# DAC_JESD204B.net
KiCad netlist of a schematic drawn in Altium Designer
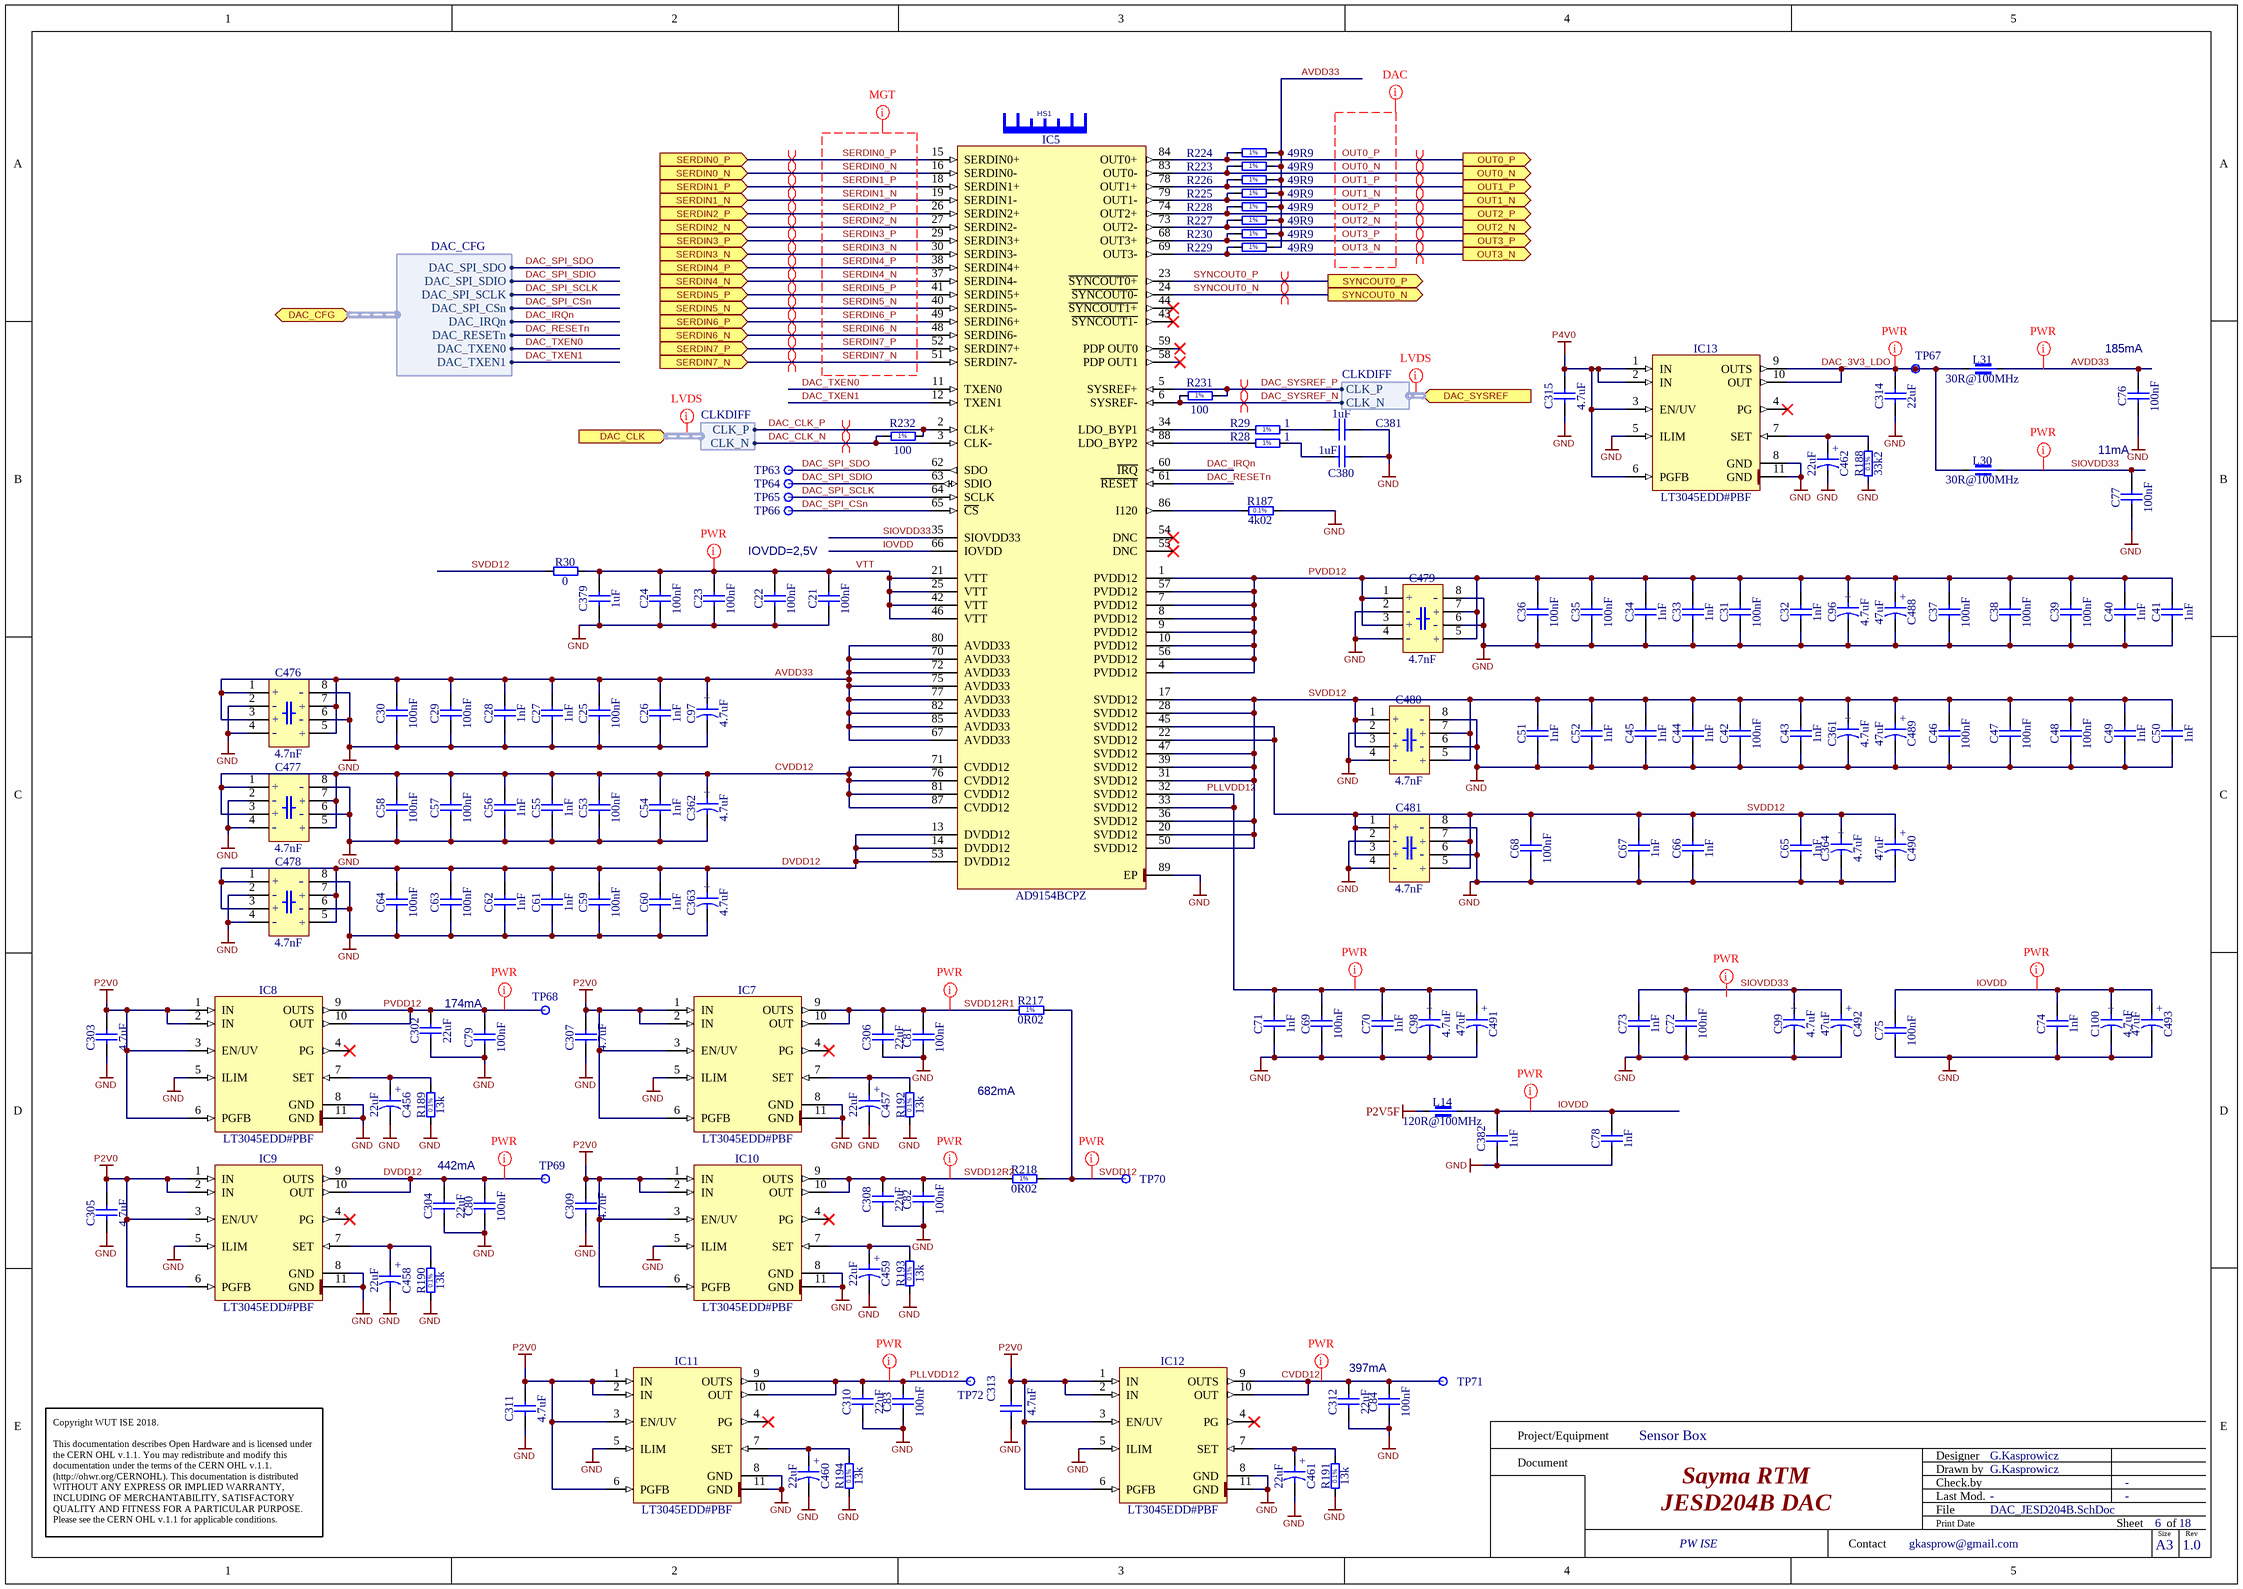
[diagram p0: DAC_JESD204B.SchDoc]

(export (version "E")
  (design (tool "Eeschema 10.0.6"))
  (components
    (comp (ref "C21")
      (value "100nF")
      (footprint "CAPC0603X33N")
      (description "Non-polarised capacitor")
      (fields
        (field (name "MANUFACTURER PART NUMBER") "CC0201_100NF_6.3V_10%_X5R")
        (field (name "MANUFACTURER") "GENERIC")
        (field (name "AUTHOR") "CERN DEM JLC")
      )
      (libsource (lib "Capacitors") (part "Capacitor - non polarized"))
    )
    (comp (ref "C22")
      (value "100nF")
      (footprint "CAPC0603X33N")
      (description "Non-polarised capacitor")
      (fields
        (field (name "MANUFACTURER PART NUMBER") "CC0201_100NF_6.3V_10%_X5R")
        (field (name "MANUFACTURER") "GENERIC")
        (field (name "AUTHOR") "CERN DEM JLC")
      )
      (libsource (lib "Capacitors") (part "Capacitor - non polarized"))
    )
    (comp (ref "C23")
      (value "100nF")
      (footprint "CAPC0603X33N")
      (description "Non-polarised capacitor")
      (fields
        (field (name "MANUFACTURER PART NUMBER") "CC0201_100NF_6.3V_10%_X5R")
        (field (name "MANUFACTURER") "GENERIC")
        (field (name "AUTHOR") "CERN DEM JLC")
      )
      (libsource (lib "Capacitors") (part "Capacitor - non polarized"))
    )
    (comp (ref "C24")
      (value "100nF")
      (footprint "CAPC0603X33N")
      (description "Non-polarised capacitor")
      (fields
        (field (name "MANUFACTURER PART NUMBER") "CC0201_100NF_6.3V_10%_X5R")
        (field (name "MANUFACTURER") "GENERIC")
        (field (name "AUTHOR") "CERN DEM JLC")
      )
      (libsource (lib "Capacitors") (part "Capacitor - non polarized"))
    )
    (comp (ref "C25")
      (value "100nF")
      (footprint "CAPC0603X33N")
      (description "Non-polarised capacitor")
      (fields
        (field (name "MANUFACTURER PART NUMBER") "CC0201_100NF_6.3V_10%_X5R")
        (field (name "MANUFACTURER") "GENERIC")
        (field (name "AUTHOR") "CERN DEM JLC")
      )
      (libsource (lib "Capacitors") (part "Capacitor - non polarized"))
    )
    (comp (ref "C26")
      (value "1nF")
      (footprint "CAPC0603X33N")
      (description "Non-polarised capacitor")
      (fields
        (field (name "MANUFACTURER PART NUMBER") "CC0201_1NF_16V_10%_X5R")
        (field (name "MANUFACTURER") "GENERIC")
        (field (name "AUTHOR") "CERN DEM JLC")
      )
      (libsource (lib "Capacitors") (part "Capacitor - non polarized"))
    )
    (comp (ref "C27")
      (value "1nF")
      (footprint "CAPC0603X33N")
      (description "Non-polarised capacitor")
      (fields
        (field (name "MANUFACTURER PART NUMBER") "CC0201_1NF_16V_10%_X5R")
        (field (name "MANUFACTURER") "GENERIC")
        (field (name "AUTHOR") "CERN DEM JLC")
      )
      (libsource (lib "Capacitors") (part "Capacitor - non polarized"))
    )
    (comp (ref "C28")
      (value "1nF")
      (footprint "CAPC0603X33N")
      (description "Non-polarised capacitor")
      (fields
        (field (name "MANUFACTURER PART NUMBER") "CC0201_1NF_16V_10%_X5R")
        (field (name "MANUFACTURER") "GENERIC")
        (field (name "AUTHOR") "CERN DEM JLC")
      )
      (libsource (lib "Capacitors") (part "Capacitor - non polarized"))
    )
    (comp (ref "C29")
      (value "100nF")
      (footprint "CAPC0603X33N")
      (description "Non-polarised capacitor")
      (fields
        (field (name "MANUFACTURER PART NUMBER") "CC0201_100NF_6.3V_10%_X5R")
        (field (name "MANUFACTURER") "GENERIC")
        (field (name "AUTHOR") "CERN DEM JLC")
      )
      (libsource (lib "Capacitors") (part "Capacitor - non polarized"))
    )
    (comp (ref "C30")
      (value "100nF")
      (footprint "CAPC0603X33N")
      (description "Non-polarised capacitor")
      (fields
        (field (name "MANUFACTURER PART NUMBER") "CC0201_100NF_6.3V_10%_X5R")
        (field (name "MANUFACTURER") "GENERIC")
        (field (name "AUTHOR") "CERN DEM JLC")
      )
      (libsource (lib "Capacitors") (part "Capacitor - non polarized"))
    )
    (comp (ref "C31")
      (value "100nF")
      (footprint "CAPC0603X33N")
      (description "Non-polarised capacitor")
      (fields
        (field (name "MANUFACTURER PART NUMBER") "CC0201_100NF_6.3V_10%_X5R")
        (field (name "MANUFACTURER") "GENERIC")
        (field (name "AUTHOR") "CERN DEM JLC")
      )
      (libsource (lib "Capacitors") (part "Capacitor - non polarized"))
    )
    (comp (ref "C32")
      (value "1nF")
      (footprint "CAPC0603X33N")
      (description "Non-polarised capacitor")
      (fields
        (field (name "MANUFACTURER PART NUMBER") "CC0201_1NF_16V_10%_X5R")
        (field (name "MANUFACTURER") "GENERIC")
        (field (name "AUTHOR") "CERN DEM JLC")
      )
      (libsource (lib "Capacitors") (part "Capacitor - non polarized"))
    )
    (comp (ref "C33")
      (value "1nF")
      (footprint "CAPC0603X33N")
      (description "Non-polarised capacitor")
      (fields
        (field (name "MANUFACTURER PART NUMBER") "CC0201_1NF_16V_10%_X5R")
        (field (name "MANUFACTURER") "GENERIC")
        (field (name "AUTHOR") "CERN DEM JLC")
      )
      (libsource (lib "Capacitors") (part "Capacitor - non polarized"))
    )
    (comp (ref "C34")
      (value "1nF")
      (footprint "CAPC0603X33N")
      (description "Non-polarised capacitor")
      (fields
        (field (name "MANUFACTURER PART NUMBER") "CC0201_1NF_16V_10%_X5R")
        (field (name "MANUFACTURER") "GENERIC")
        (field (name "AUTHOR") "CERN DEM JLC")
      )
      (libsource (lib "Capacitors") (part "Capacitor - non polarized"))
    )
    (comp (ref "C35")
      (value "100nF")
      (footprint "CAPC0603X33N")
      (description "Non-polarised capacitor")
      (fields
        (field (name "MANUFACTURER PART NUMBER") "CC0201_100NF_6.3V_10%_X5R")
        (field (name "MANUFACTURER") "GENERIC")
        (field (name "AUTHOR") "CERN DEM JLC")
      )
      (libsource (lib "Capacitors") (part "Capacitor - non polarized"))
    )
    (comp (ref "C36")
      (value "100nF")
      (footprint "CAPC0603X33N")
      (description "Non-polarised capacitor")
      (fields
        (field (name "MANUFACTURER PART NUMBER") "CC0201_100NF_6.3V_10%_X5R")
        (field (name "MANUFACTURER") "GENERIC")
        (field (name "AUTHOR") "CERN DEM JLC")
      )
      (libsource (lib "Capacitors") (part "Capacitor - non polarized"))
    )
    (comp (ref "C37")
      (value "100nF")
      (footprint "CAPC0603X33N")
      (description "Non-polarised capacitor")
      (fields
        (field (name "MANUFACTURER PART NUMBER") "CC0201_100NF_6.3V_10%_X5R")
        (field (name "MANUFACTURER") "GENERIC")
        (field (name "AUTHOR") "CERN DEM JLC")
      )
      (libsource (lib "Capacitors") (part "Capacitor - non polarized"))
    )
    (comp (ref "C38")
      (value "100nF")
      (footprint "CAPC0603X33N")
      (description "Non-polarised capacitor")
      (fields
        (field (name "MANUFACTURER PART NUMBER") "CC0201_100NF_6.3V_10%_X5R")
        (field (name "MANUFACTURER") "GENERIC")
        (field (name "AUTHOR") "CERN DEM JLC")
      )
      (libsource (lib "Capacitors") (part "Capacitor - non polarized"))
    )
    (comp (ref "C39")
      (value "100nF")
      (footprint "CAPC0603X33N")
      (description "Non-polarised capacitor")
      (fields
        (field (name "MANUFACTURER PART NUMBER") "CC0201_100NF_6.3V_10%_X5R")
        (field (name "MANUFACTURER") "GENERIC")
        (field (name "AUTHOR") "CERN DEM JLC")
      )
      (libsource (lib "Capacitors") (part "Capacitor - non polarized"))
    )
    (comp (ref "C40")
      (value "1nF")
      (footprint "CAPC0603X33N")
      (description "Non-polarised capacitor")
      (fields
        (field (name "MANUFACTURER PART NUMBER") "CC0201_1NF_16V_10%_X5R")
        (field (name "MANUFACTURER") "GENERIC")
        (field (name "AUTHOR") "CERN DEM JLC")
      )
      (libsource (lib "Capacitors") (part "Capacitor - non polarized"))
    )
    (comp (ref "C41")
      (value "1nF")
      (footprint "CAPC0603X33N")
      (description "Non-polarised capacitor")
      (fields
        (field (name "MANUFACTURER PART NUMBER") "CC0201_1NF_16V_10%_X5R")
        (field (name "MANUFACTURER") "GENERIC")
        (field (name "AUTHOR") "CERN DEM JLC")
      )
      (libsource (lib "Capacitors") (part "Capacitor - non polarized"))
    )
    (comp (ref "C42")
      (value "100nF")
      (footprint "CAPC0603X33N")
      (description "Non-polarised capacitor")
      (fields
        (field (name "MANUFACTURER PART NUMBER") "CC0201_100NF_6.3V_10%_X5R")
        (field (name "MANUFACTURER") "GENERIC")
        (field (name "AUTHOR") "CERN DEM JLC")
      )
      (libsource (lib "Capacitors") (part "Capacitor - non polarized"))
    )
    (comp (ref "C43")
      (value "1nF")
      (footprint "CAPC0603X33N")
      (description "Non-polarised capacitor")
      (fields
        (field (name "MANUFACTURER PART NUMBER") "CC0201_1NF_16V_10%_X5R")
        (field (name "MANUFACTURER") "GENERIC")
        (field (name "AUTHOR") "CERN DEM JLC")
      )
      (libsource (lib "Capacitors") (part "Capacitor - non polarized"))
    )
    (comp (ref "C44")
      (value "1nF")
      (footprint "CAPC0603X33N")
      (description "Non-polarised capacitor")
      (fields
        (field (name "MANUFACTURER PART NUMBER") "CC0201_1NF_16V_10%_X5R")
        (field (name "MANUFACTURER") "GENERIC")
        (field (name "AUTHOR") "CERN DEM JLC")
      )
      (libsource (lib "Capacitors") (part "Capacitor - non polarized"))
    )
    (comp (ref "C45")
      (value "1nF")
      (footprint "CAPC0603X33N")
      (description "Non-polarised capacitor")
      (fields
        (field (name "MANUFACTURER PART NUMBER") "CC0201_1NF_16V_10%_X5R")
        (field (name "MANUFACTURER") "GENERIC")
        (field (name "AUTHOR") "CERN DEM JLC")
      )
      (libsource (lib "Capacitors") (part "Capacitor - non polarized"))
    )
    (comp (ref "C46")
      (value "100nF")
      (footprint "CAPC0603X33N")
      (description "Non-polarised capacitor")
      (fields
        (field (name "MANUFACTURER PART NUMBER") "CC0201_100NF_6.3V_10%_X5R")
        (field (name "MANUFACTURER") "GENERIC")
        (field (name "AUTHOR") "CERN DEM JLC")
      )
      (libsource (lib "Capacitors") (part "Capacitor - non polarized"))
    )
    (comp (ref "C47")
      (value "100nF")
      (footprint "CAPC0603X33N")
      (description "Non-polarised capacitor")
      (fields
        (field (name "MANUFACTURER PART NUMBER") "CC0201_100NF_6.3V_10%_X5R")
        (field (name "MANUFACTURER") "GENERIC")
        (field (name "AUTHOR") "CERN DEM JLC")
      )
      (libsource (lib "Capacitors") (part "Capacitor - non polarized"))
    )
    (comp (ref "C48")
      (value "100nF")
      (footprint "CAPC0603X33N")
      (description "Non-polarised capacitor")
      (fields
        (field (name "MANUFACTURER PART NUMBER") "CC0201_100NF_6.3V_10%_X5R")
        (field (name "MANUFACTURER") "GENERIC")
        (field (name "AUTHOR") "CERN DEM JLC")
      )
      (libsource (lib "Capacitors") (part "Capacitor - non polarized"))
    )
    (comp (ref "C49")
      (value "1nF")
      (footprint "CAPC0603X33N")
      (description "Non-polarised capacitor")
      (fields
        (field (name "MANUFACTURER PART NUMBER") "CC0201_1NF_16V_10%_X5R")
        (field (name "MANUFACTURER") "GENERIC")
        (field (name "AUTHOR") "CERN DEM JLC")
      )
      (libsource (lib "Capacitors") (part "Capacitor - non polarized"))
    )
    (comp (ref "C50")
      (value "1nF")
      (footprint "CAPC0603X33N")
      (description "Non-polarised capacitor")
      (fields
        (field (name "MANUFACTURER PART NUMBER") "CC0201_1NF_16V_10%_X5R")
        (field (name "MANUFACTURER") "GENERIC")
        (field (name "AUTHOR") "CERN DEM JLC")
      )
      (libsource (lib "Capacitors") (part "Capacitor - non polarized"))
    )
    (comp (ref "C51")
      (value "1nF")
      (footprint "CAPC0603X33N")
      (description "Non-polarised capacitor")
      (fields
        (field (name "MANUFACTURER PART NUMBER") "CC0201_1NF_16V_10%_X5R")
        (field (name "MANUFACTURER") "GENERIC")
        (field (name "AUTHOR") "CERN DEM JLC")
      )
      (libsource (lib "Capacitors") (part "Capacitor - non polarized"))
    )
    (comp (ref "C52")
      (value "1nF")
      (footprint "CAPC0603X33N")
      (description "Non-polarised capacitor")
      (fields
        (field (name "MANUFACTURER PART NUMBER") "CC0201_1NF_16V_10%_X5R")
        (field (name "MANUFACTURER") "GENERIC")
        (field (name "AUTHOR") "CERN DEM JLC")
      )
      (libsource (lib "Capacitors") (part "Capacitor - non polarized"))
    )
    (comp (ref "C53")
      (value "100nF")
      (footprint "CAPC0603X33N")
      (description "Non-polarised capacitor")
      (fields
        (field (name "MANUFACTURER PART NUMBER") "CC0201_100NF_6.3V_10%_X5R")
        (field (name "MANUFACTURER") "GENERIC")
        (field (name "AUTHOR") "CERN DEM JLC")
      )
      (libsource (lib "Capacitors") (part "Capacitor - non polarized"))
    )
    (comp (ref "C54")
      (value "1nF")
      (footprint "CAPC0603X33N")
      (description "Non-polarised capacitor")
      (fields
        (field (name "MANUFACTURER PART NUMBER") "CC0201_1NF_16V_10%_X5R")
        (field (name "MANUFACTURER") "GENERIC")
        (field (name "AUTHOR") "CERN DEM JLC")
      )
      (libsource (lib "Capacitors") (part "Capacitor - non polarized"))
    )
    (comp (ref "C55")
      (value "1nF")
      (footprint "CAPC0603X33N")
      (description "Non-polarised capacitor")
      (fields
        (field (name "MANUFACTURER PART NUMBER") "CC0201_1NF_16V_10%_X5R")
        (field (name "MANUFACTURER") "GENERIC")
        (field (name "AUTHOR") "CERN DEM JLC")
      )
      (libsource (lib "Capacitors") (part "Capacitor - non polarized"))
    )
    (comp (ref "C56")
      (value "1nF")
      (footprint "CAPC0603X33N")
      (description "Non-polarised capacitor")
      (fields
        (field (name "MANUFACTURER PART NUMBER") "CC0201_1NF_16V_10%_X5R")
        (field (name "MANUFACTURER") "GENERIC")
        (field (name "AUTHOR") "CERN DEM JLC")
      )
      (libsource (lib "Capacitors") (part "Capacitor - non polarized"))
    )
    (comp (ref "C57")
      (value "100nF")
      (footprint "CAPC0603X33N")
      (description "Non-polarised capacitor")
      (fields
        (field (name "MANUFACTURER PART NUMBER") "CC0201_100NF_6.3V_10%_X5R")
        (field (name "MANUFACTURER") "GENERIC")
        (field (name "AUTHOR") "CERN DEM JLC")
      )
      (libsource (lib "Capacitors") (part "Capacitor - non polarized"))
    )
    (comp (ref "C58")
      (value "100nF")
      (footprint "CAPC0603X33N")
      (description "Non-polarised capacitor")
      (fields
        (field (name "MANUFACTURER PART NUMBER") "CC0201_100NF_6.3V_10%_X5R")
        (field (name "MANUFACTURER") "GENERIC")
        (field (name "AUTHOR") "CERN DEM JLC")
      )
      (libsource (lib "Capacitors") (part "Capacitor - non polarized"))
    )
    (comp (ref "C59")
      (value "100nF")
      (footprint "CAPC0603X33N")
      (description "Non-polarised capacitor")
      (fields
        (field (name "MANUFACTURER PART NUMBER") "CC0201_100NF_6.3V_10%_X5R")
        (field (name "MANUFACTURER") "GENERIC")
        (field (name "AUTHOR") "CERN DEM JLC")
      )
      (libsource (lib "Capacitors") (part "Capacitor - non polarized"))
    )
    (comp (ref "C60")
      (value "1nF")
      (footprint "CAPC0603X33N")
      (description "Non-polarised capacitor")
      (fields
        (field (name "MANUFACTURER PART NUMBER") "CC0201_1NF_16V_10%_X5R")
        (field (name "MANUFACTURER") "GENERIC")
        (field (name "AUTHOR") "CERN DEM JLC")
      )
      (libsource (lib "Capacitors") (part "Capacitor - non polarized"))
    )
    (comp (ref "C61")
      (value "1nF")
      (footprint "CAPC0603X33N")
      (description "Non-polarised capacitor")
      (fields
        (field (name "MANUFACTURER PART NUMBER") "CC0201_1NF_16V_10%_X5R")
        (field (name "MANUFACTURER") "GENERIC")
        (field (name "AUTHOR") "CERN DEM JLC")
      )
      (libsource (lib "Capacitors") (part "Capacitor - non polarized"))
    )
    (comp (ref "C62")
      (value "1nF")
      (footprint "CAPC0603X33N")
      (description "Non-polarised capacitor")
      (fields
        (field (name "MANUFACTURER PART NUMBER") "CC0201_1NF_16V_10%_X5R")
        (field (name "MANUFACTURER") "GENERIC")
        (field (name "AUTHOR") "CERN DEM JLC")
      )
      (libsource (lib "Capacitors") (part "Capacitor - non polarized"))
    )
    (comp (ref "C63")
      (value "100nF")
      (footprint "CAPC0603X33N")
      (description "Non-polarised capacitor")
      (fields
        (field (name "MANUFACTURER PART NUMBER") "CC0201_100NF_6.3V_10%_X5R")
        (field (name "MANUFACTURER") "GENERIC")
        (field (name "AUTHOR") "CERN DEM JLC")
      )
      (libsource (lib "Capacitors") (part "Capacitor - non polarized"))
    )
    (comp (ref "C64")
      (value "100nF")
      (footprint "CAPC0603X33N")
      (description "Non-polarised capacitor")
      (fields
        (field (name "MANUFACTURER PART NUMBER") "CC0201_100NF_6.3V_10%_X5R")
        (field (name "MANUFACTURER") "GENERIC")
        (field (name "AUTHOR") "CERN DEM JLC")
      )
      (libsource (lib "Capacitors") (part "Capacitor - non polarized"))
    )
    (comp (ref "C65")
      (value "1nF")
      (footprint "CAPC0603X33N")
      (description "Non-polarised capacitor")
      (fields
        (field (name "MANUFACTURER PART NUMBER") "CC0201_1NF_16V_10%_X5R")
        (field (name "MANUFACTURER") "GENERIC")
        (field (name "AUTHOR") "CERN DEM JLC")
      )
      (libsource (lib "Capacitors") (part "Capacitor - non polarized"))
    )
    (comp (ref "C66")
      (value "1nF")
      (footprint "CAPC0603X33N")
      (description "Non-polarised capacitor")
      (fields
        (field (name "MANUFACTURER PART NUMBER") "CC0201_1NF_16V_10%_X5R")
        (field (name "MANUFACTURER") "GENERIC")
        (field (name "AUTHOR") "CERN DEM JLC")
      )
      (libsource (lib "Capacitors") (part "Capacitor - non polarized"))
    )
    (comp (ref "C67")
      (value "1nF")
      (footprint "CAPC0603X33N")
      (description "Non-polarised capacitor")
      (fields
        (field (name "MANUFACTURER PART NUMBER") "CC0201_1NF_16V_10%_X5R")
        (field (name "MANUFACTURER") "GENERIC")
        (field (name "AUTHOR") "CERN DEM JLC")
      )
      (libsource (lib "Capacitors") (part "Capacitor - non polarized"))
    )
    (comp (ref "C68")
      (value "100nF")
      (footprint "CAPC0603X33N")
      (description "Non-polarised capacitor")
      (fields
        (field (name "MANUFACTURER PART NUMBER") "CC0201_100NF_6.3V_10%_X5R")
        (field (name "MANUFACTURER") "GENERIC")
        (field (name "AUTHOR") "CERN DEM JLC")
      )
      (libsource (lib "Capacitors") (part "Capacitor - non polarized"))
    )
    (comp (ref "C69")
      (value "100nF")
      (footprint "CAPC0603X33N")
      (description "Non-polarised capacitor")
      (fields
        (field (name "MANUFACTURER PART NUMBER") "CC0201_100NF_6.3V_10%_X5R")
        (field (name "MANUFACTURER") "GENERIC")
        (field (name "AUTHOR") "CERN DEM JLC")
      )
      (libsource (lib "Capacitors") (part "Capacitor - non polarized"))
    )
    (comp (ref "C70")
      (value "1nF")
      (footprint "CAPC0603X33N")
      (description "Non-polarised capacitor")
      (fields
        (field (name "MANUFACTURER PART NUMBER") "CC0201_1NF_16V_10%_X5R")
        (field (name "MANUFACTURER") "GENERIC")
        (field (name "AUTHOR") "CERN DEM JLC")
      )
      (libsource (lib "Capacitors") (part "Capacitor - non polarized"))
    )
    (comp (ref "C71")
      (value "1nF")
      (footprint "CAPC0603X33N")
      (description "Non-polarised capacitor")
      (fields
        (field (name "MANUFACTURER PART NUMBER") "CC0201_1NF_16V_10%_X5R")
        (field (name "MANUFACTURER") "GENERIC")
        (field (name "AUTHOR") "CERN DEM JLC")
      )
      (libsource (lib "Capacitors") (part "Capacitor - non polarized"))
    )
    (comp (ref "C72")
      (value "100nF")
      (footprint "CAPC0603X33N")
      (description "Non-polarised capacitor")
      (fields
        (field (name "MANUFACTURER PART NUMBER") "CC0201_100NF_6.3V_10%_X5R")
        (field (name "MANUFACTURER") "GENERIC")
        (field (name "AUTHOR") "CERN DEM JLC")
      )
      (libsource (lib "Capacitors") (part "Capacitor - non polarized"))
    )
    (comp (ref "C73")
      (value "1nF")
      (footprint "CAPC0603X33N")
      (description "Non-polarised capacitor")
      (fields
        (field (name "MANUFACTURER PART NUMBER") "CC0201_1NF_16V_10%_X5R")
        (field (name "MANUFACTURER") "GENERIC")
        (field (name "AUTHOR") "CERN DEM JLC")
      )
      (libsource (lib "Capacitors") (part "Capacitor - non polarized"))
    )
    (comp (ref "C74")
      (value "1nF")
      (footprint "CAPC0603X33N")
      (description "Non-polarised capacitor")
      (fields
        (field (name "MANUFACTURER PART NUMBER") "CC0201_1NF_16V_10%_X5R")
        (field (name "MANUFACTURER") "GENERIC")
        (field (name "AUTHOR") "CERN DEM JLC")
      )
      (libsource (lib "Capacitors") (part "Capacitor - non polarized"))
    )
    (comp (ref "C75")
      (value "100nF")
      (footprint "CAPC0603X33N")
      (description "Non-polarised capacitor")
      (fields
        (field (name "MANUFACTURER PART NUMBER") "CC0201_100NF_6.3V_10%_X5R")
        (field (name "MANUFACTURER") "GENERIC")
        (field (name "AUTHOR") "CERN DEM JLC")
      )
      (libsource (lib "Capacitors") (part "Capacitor - non polarized"))
    )
    (comp (ref "C76")
      (value "100nF")
      (footprint "CAPC0603X33N")
      (description "Non-polarised capacitor")
      (fields
        (field (name "MANUFACTURER PART NUMBER") "CC0201_100NF_6.3V_10%_X5R")
        (field (name "MANUFACTURER") "GENERIC")
        (field (name "AUTHOR") "CERN DEM JLC")
      )
      (libsource (lib "Capacitors") (part "Capacitor - non polarized"))
    )
    (comp (ref "C77")
      (value "100nF")
      (footprint "CAPC0603X33N")
      (description "Non-polarised capacitor")
      (fields
        (field (name "MANUFACTURER PART NUMBER") "CC0201_100NF_6.3V_10%_X5R")
        (field (name "MANUFACTURER") "GENERIC")
        (field (name "AUTHOR") "CERN DEM JLC")
      )
      (libsource (lib "Capacitors") (part "Capacitor - non polarized"))
    )
    (comp (ref "C78")
      (value "1nF")
      (footprint "CAPC0603X33N")
      (description "Non-polarised capacitor")
      (fields
        (field (name "MANUFACTURER PART NUMBER") "CC0201_1NF_16V_10%_X5R")
        (field (name "MANUFACTURER") "GENERIC")
        (field (name "AUTHOR") "CERN DEM JLC")
      )
      (libsource (lib "Capacitors") (part "Capacitor - non polarized"))
    )
    (comp (ref "C79")
      (value "100nF")
      (footprint "CAPC0603X33N")
      (description "Non-polarised capacitor")
      (fields
        (field (name "MANUFACTURER PART NUMBER") "CC0201_100NF_6.3V_10%_X5R")
        (field (name "MANUFACTURER") "GENERIC")
        (field (name "AUTHOR") "CERN DEM JLC")
      )
      (libsource (lib "Capacitors") (part "Capacitor - non polarized"))
    )
    (comp (ref "C80")
      (value "100nF")
      (footprint "CAPC0603X33N")
      (description "Non-polarised capacitor")
      (fields
        (field (name "MANUFACTURER PART NUMBER") "CC0201_100NF_6.3V_10%_X5R")
        (field (name "MANUFACTURER") "GENERIC")
        (field (name "AUTHOR") "CERN DEM JLC")
      )
      (libsource (lib "Capacitors") (part "Capacitor - non polarized"))
    )
    (comp (ref "C81")
      (value "100nF")
      (footprint "CAPC0603X33N")
      (description "Non-polarised capacitor")
      (fields
        (field (name "MANUFACTURER PART NUMBER") "CC0201_100NF_6.3V_10%_X5R")
        (field (name "MANUFACTURER") "GENERIC")
        (field (name "AUTHOR") "CERN DEM JLC")
      )
      (libsource (lib "Capacitors") (part "Capacitor - non polarized"))
    )
    (comp (ref "C82")
      (value "100nF")
      (footprint "CAPC0603X33N")
      (description "Non-polarised capacitor")
      (fields
        (field (name "MANUFACTURER PART NUMBER") "CC0201_100NF_6.3V_10%_X5R")
        (field (name "MANUFACTURER") "GENERIC")
        (field (name "AUTHOR") "CERN DEM JLC")
      )
      (libsource (lib "Capacitors") (part "Capacitor - non polarized"))
    )
    (comp (ref "C83")
      (value "100nF")
      (footprint "CAPC0603X33N")
      (description "Non-polarised capacitor")
      (fields
        (field (name "MANUFACTURER PART NUMBER") "CC0201_100NF_6.3V_10%_X5R")
        (field (name "MANUFACTURER") "GENERIC")
        (field (name "AUTHOR") "CERN DEM JLC")
      )
      (libsource (lib "Capacitors") (part "Capacitor - non polarized"))
    )
    (comp (ref "C84")
      (value "100nF")
      (footprint "CAPC0603X33N")
      (description "Non-polarised capacitor")
      (fields
        (field (name "MANUFACTURER PART NUMBER") "CC0201_100NF_6.3V_10%_X5R")
        (field (name "MANUFACTURER") "GENERIC")
        (field (name "AUTHOR") "CERN DEM JLC")
      )
      (libsource (lib "Capacitors") (part "Capacitor - non polarized"))
    )
    (comp (ref "C96")
      (value "4.7uF")
      (footprint "CAPMP3528X210N")
      (description "Polarised capacitor")
      (fields
        (field (name "MANUFACTURER PART NUMBER") "CTE3528-21_4.7UF_35V_10%")
        (field (name "MANUFACTURER") "GENERIC")
        (field (name "AUTHOR") "CERN DEM JLC")
      )
      (libsource (lib "") (part "Capacitor - polarized_1"))
    )
    (comp (ref "C97")
      (value "4.7uF")
      (footprint "CAPMP3528X210N")
      (description "Polarised capacitor")
      (fields
        (field (name "MANUFACTURER PART NUMBER") "CTE3528-21_4.7UF_35V_10%")
        (field (name "MANUFACTURER") "GENERIC")
        (field (name "AUTHOR") "CERN DEM JLC")
      )
      (libsource (lib "") (part "Capacitor - polarized_1"))
    )
    (comp (ref "C98")
      (value "4.7uF")
      (footprint "CAPMP3528X210N")
      (description "Polarised capacitor")
      (fields
        (field (name "MANUFACTURER PART NUMBER") "CTE3528-21_4.7UF_35V_10%")
        (field (name "MANUFACTURER") "GENERIC")
        (field (name "AUTHOR") "CERN DEM JLC")
      )
      (libsource (lib "") (part "Capacitor - polarized_1"))
    )
    (comp (ref "C99")
      (value "4.7uF")
      (footprint "CAPMP3528X210N")
      (description "Polarised capacitor")
      (fields
        (field (name "MANUFACTURER PART NUMBER") "CTE3528-21_4.7UF_35V_10%")
        (field (name "MANUFACTURER") "GENERIC")
        (field (name "AUTHOR") "CERN DEM JLC")
      )
      (libsource (lib "") (part "Capacitor - polarized_1"))
    )
    (comp (ref "C100")
      (value "4.7uF")
      (footprint "CAPMP3528X210N")
      (description "Polarised capacitor")
      (fields
        (field (name "MANUFACTURER PART NUMBER") "CTE3528-21_4.7UF_35V_10%")
        (field (name "MANUFACTURER") "GENERIC")
        (field (name "AUTHOR") "CERN DEM JLC")
      )
      (libsource (lib "") (part "Capacitor - polarized_1"))
    )
    (comp (ref "C302")
      (value "22uF")
      (footprint "CAPC2012X135N")
      (description "Non-polarised capacitor")
      (fields
        (field (name "MANUFACTURER PART NUMBER") "CC0805_22UF_16V_10%_X5R")
        (field (name "MANUFACTURER") "GENERIC")
        (field (name "AUTHOR") "CERN DEM JLC")
      )
      (libsource (lib "Capacitors") (part "Capacitor - non polarized"))
    )
    (comp (ref "C303")
      (value "4.7uF")
      (footprint "CAPC1608X90N")
      (description "Non-polarised capacitor")
      (fields
        (field (name "MANUFACTURER PART NUMBER") "CC0603_4.7UF_25V_10%_X5R")
        (field (name "MANUFACTURER") "GENERIC")
        (field (name "AUTHOR") "CERN DEM JLC")
      )
      (libsource (lib "Capacitors") (part "Capacitor - non polarized"))
    )
    (comp (ref "C304")
      (value "22uF")
      (footprint "CAPC2012X135N")
      (description "Non-polarised capacitor")
      (fields
        (field (name "MANUFACTURER PART NUMBER") "CC0805_22UF_16V_10%_X5R")
        (field (name "MANUFACTURER") "GENERIC")
        (field (name "AUTHOR") "CERN DEM JLC")
      )
      (libsource (lib "Capacitors") (part "Capacitor - non polarized"))
    )
    (comp (ref "C305")
      (value "4.7uF")
      (footprint "CAPC1608X90N")
      (description "Non-polarised capacitor")
      (fields
        (field (name "MANUFACTURER PART NUMBER") "CC0603_4.7UF_25V_10%_X5R")
        (field (name "MANUFACTURER") "GENERIC")
        (field (name "AUTHOR") "CERN DEM JLC")
      )
      (libsource (lib "Capacitors") (part "Capacitor - non polarized"))
    )
    (comp (ref "C306")
      (value "22uF")
      (footprint "CAPC2012X135N")
      (description "Non-polarised capacitor")
      (fields
        (field (name "MANUFACTURER PART NUMBER") "CC0805_22UF_16V_10%_X5R")
        (field (name "MANUFACTURER") "GENERIC")
        (field (name "AUTHOR") "CERN DEM JLC")
      )
      (libsource (lib "Capacitors") (part "Capacitor - non polarized"))
    )
    (comp (ref "C307")
      (value "4.7uF")
      (footprint "CAPC1608X90N")
      (description "Non-polarised capacitor")
      (fields
        (field (name "MANUFACTURER PART NUMBER") "CC0603_4.7UF_25V_10%_X5R")
        (field (name "MANUFACTURER") "GENERIC")
        (field (name "AUTHOR") "CERN DEM JLC")
      )
      (libsource (lib "Capacitors") (part "Capacitor - non polarized"))
    )
    (comp (ref "C308")
      (value "22uF")
      (footprint "CAPC2012X135N")
      (description "Non-polarised capacitor")
      (fields
        (field (name "MANUFACTURER PART NUMBER") "CC0805_22UF_16V_10%_X5R")
        (field (name "MANUFACTURER") "GENERIC")
        (field (name "AUTHOR") "CERN DEM JLC")
      )
      (libsource (lib "Capacitors") (part "Capacitor - non polarized"))
    )
    (comp (ref "C309")
      (value "4.7uF")
      (footprint "CAPC1608X90N")
      (description "Non-polarised capacitor")
      (fields
        (field (name "MANUFACTURER PART NUMBER") "CC0603_4.7UF_25V_10%_X5R")
        (field (name "MANUFACTURER") "GENERIC")
        (field (name "AUTHOR") "CERN DEM JLC")
      )
      (libsource (lib "Capacitors") (part "Capacitor - non polarized"))
    )
    (comp (ref "C310")
      (value "22uF")
      (footprint "CAPC2012X135N")
      (description "Non-polarised capacitor")
      (fields
        (field (name "MANUFACTURER PART NUMBER") "CC0805_22UF_16V_10%_X5R")
        (field (name "MANUFACTURER") "GENERIC")
        (field (name "AUTHOR") "CERN DEM JLC")
      )
      (libsource (lib "Capacitors") (part "Capacitor - non polarized"))
    )
    (comp (ref "C311")
      (value "4.7uF")
      (footprint "CAPC1608X90N")
      (description "Non-polarised capacitor")
      (fields
        (field (name "MANUFACTURER PART NUMBER") "CC0603_4.7UF_25V_10%_X5R")
        (field (name "MANUFACTURER") "GENERIC")
        (field (name "AUTHOR") "CERN DEM JLC")
      )
      (libsource (lib "Capacitors") (part "Capacitor - non polarized"))
    )
    (comp (ref "C312")
      (value "22uF")
      (footprint "CAPC2012X135N")
      (description "Non-polarised capacitor")
      (fields
        (field (name "MANUFACTURER PART NUMBER") "CC0805_22UF_16V_10%_X5R")
        (field (name "MANUFACTURER") "GENERIC")
        (field (name "AUTHOR") "CERN DEM JLC")
      )
      (libsource (lib "Capacitors") (part "Capacitor - non polarized"))
    )
    (comp (ref "C313")
      (value "4.7uF")
      (footprint "CAPC1608X90N")
      (description "Non-polarised capacitor")
      (fields
        (field (name "MANUFACTURER PART NUMBER") "CC0603_4.7UF_25V_10%_X5R")
        (field (name "MANUFACTURER") "GENERIC")
        (field (name "AUTHOR") "CERN DEM JLC")
      )
      (libsource (lib "Capacitors") (part "Capacitor - non polarized"))
    )
    (comp (ref "C314")
      (value "22uF")
      (footprint "CAPC2012X135N")
      (description "Non-polarised capacitor")
      (fields
        (field (name "MANUFACTURER PART NUMBER") "CC0805_22UF_16V_10%_X5R")
        (field (name "MANUFACTURER") "GENERIC")
        (field (name "AUTHOR") "CERN DEM JLC")
      )
      (libsource (lib "Capacitors") (part "Capacitor - non polarized"))
    )
    (comp (ref "C315")
      (value "4.7uF")
      (footprint "CAPC1608X90N")
      (description "Non-polarised capacitor")
      (fields
        (field (name "MANUFACTURER PART NUMBER") "CC0603_4.7UF_25V_10%_X5R")
        (field (name "MANUFACTURER") "GENERIC")
        (field (name "AUTHOR") "CERN DEM JLC")
      )
      (libsource (lib "Capacitors") (part "Capacitor - non polarized"))
    )
    (comp (ref "C361")
      (value "4.7uF")
      (footprint "CAPMP3528X210N")
      (description "Polarised capacitor")
      (fields
        (field (name "MANUFACTURER PART NUMBER") "CTE3528-21_4.7UF_35V_10%")
        (field (name "MANUFACTURER") "GENERIC")
        (field (name "AUTHOR") "CERN DEM JLC")
      )
      (libsource (lib "") (part "Capacitor - polarized_1"))
    )
    (comp (ref "C362")
      (value "4.7uF")
      (footprint "CAPMP3528X210N")
      (description "Polarised capacitor")
      (fields
        (field (name "MANUFACTURER PART NUMBER") "CTE3528-21_4.7UF_35V_10%")
        (field (name "MANUFACTURER") "GENERIC")
        (field (name "AUTHOR") "CERN DEM JLC")
      )
      (libsource (lib "") (part "Capacitor - polarized_1"))
    )
    (comp (ref "C363")
      (value "4.7uF")
      (footprint "CAPMP3528X210N")
      (description "Polarised capacitor")
      (fields
        (field (name "MANUFACTURER PART NUMBER") "CTE3528-21_4.7UF_35V_10%")
        (field (name "MANUFACTURER") "GENERIC")
        (field (name "AUTHOR") "CERN DEM JLC")
      )
      (libsource (lib "") (part "Capacitor - polarized_1"))
    )
    (comp (ref "C364")
      (value "4.7uF")
      (footprint "CAPMP3528X210N")
      (description "Polarised capacitor")
      (fields
        (field (name "MANUFACTURER PART NUMBER") "CTE3528-21_4.7UF_35V_10%")
        (field (name "MANUFACTURER") "GENERIC")
        (field (name "AUTHOR") "CERN DEM JLC")
      )
      (libsource (lib "") (part "Capacitor - polarized_1"))
    )
    (comp (ref "C379")
      (value "1uF")
      (footprint "CAPC1005X55N")
      (description "Non-polarised capacitor")
      (fields
        (field (name "MANUFACTURER PART NUMBER") "CC0402_1UF_16V_10%_X5R")
        (field (name "MANUFACTURER") "GENERIC")
        (field (name "AUTHOR") "CERN DEM JLC")
      )
      (libsource (lib "Capacitors") (part "Capacitor - non polarized"))
    )
    (comp (ref "C380")
      (value "1uF")
      (footprint "CAPC1005X55N")
      (description "Non-polarised capacitor")
      (fields
        (field (name "MANUFACTURER PART NUMBER") "CC0402_1UF_16V_10%_X5R")
        (field (name "MANUFACTURER") "GENERIC")
        (field (name "AUTHOR") "CERN DEM JLC")
      )
      (libsource (lib "Capacitors") (part "Capacitor - non polarized"))
    )
    (comp (ref "C381")
      (value "1uF")
      (footprint "CAPC1005X55N")
      (description "Non-polarised capacitor")
      (fields
        (field (name "MANUFACTURER PART NUMBER") "CC0402_1UF_16V_10%_X5R")
        (field (name "MANUFACTURER") "GENERIC")
        (field (name "AUTHOR") "CERN DEM JLC")
      )
      (libsource (lib "Capacitors") (part "Capacitor - non polarized"))
    )
    (comp (ref "C382")
      (value "1uF")
      (footprint "CAPC1005X55N")
      (description "Non-polarised capacitor")
      (fields
        (field (name "MANUFACTURER PART NUMBER") "CC0402_1UF_16V_10%_X5R")
        (field (name "MANUFACTURER") "GENERIC")
        (field (name "AUTHOR") "CERN DEM JLC")
      )
      (libsource (lib "Capacitors") (part "Capacitor - non polarized"))
    )
    (comp (ref "C456")
      (value "22uF")
      (footprint "CAPMP3216X180N")
      (description "Polarised capacitor")
      (fields
        (field (name "MANUFACTURER PART NUMBER") "CTE3216-18_22UF_6.3V_10%_LESR0900")
        (field (name "MANUFACTURER") "GENERIC")
        (field (name "AUTHOR") "CERN DEM JLC")
      )
      (libsource (lib "Capacitors") (part "Capacitor - polarized"))
    )
    (comp (ref "C457")
      (value "22uF")
      (footprint "CAPMP3216X180N")
      (description "Polarised capacitor")
      (fields
        (field (name "MANUFACTURER PART NUMBER") "CTE3216-18_22UF_6.3V_10%_LESR0900")
        (field (name "MANUFACTURER") "GENERIC")
        (field (name "AUTHOR") "CERN DEM JLC")
      )
      (libsource (lib "Capacitors") (part "Capacitor - polarized"))
    )
    (comp (ref "C458")
      (value "22uF")
      (footprint "CAPMP3216X180N")
      (description "Polarised capacitor")
      (fields
        (field (name "MANUFACTURER PART NUMBER") "CTE3216-18_22UF_6.3V_10%_LESR0900")
        (field (name "MANUFACTURER") "GENERIC")
        (field (name "AUTHOR") "CERN DEM JLC")
      )
      (libsource (lib "Capacitors") (part "Capacitor - polarized"))
    )
    (comp (ref "C459")
      (value "22uF")
      (footprint "CAPMP3216X180N")
      (description "Polarised capacitor")
      (fields
        (field (name "MANUFACTURER PART NUMBER") "CTE3216-18_22UF_6.3V_10%_LESR0900")
        (field (name "MANUFACTURER") "GENERIC")
        (field (name "AUTHOR") "CERN DEM JLC")
      )
      (libsource (lib "Capacitors") (part "Capacitor - polarized"))
    )
    (comp (ref "C460")
      (value "22uF")
      (footprint "CAPMP3216X180N")
      (description "Polarised capacitor")
      (fields
        (field (name "MANUFACTURER PART NUMBER") "CTE3216-18_22UF_6.3V_10%_LESR0900")
        (field (name "MANUFACTURER") "GENERIC")
        (field (name "AUTHOR") "CERN DEM JLC")
      )
      (libsource (lib "Capacitors") (part "Capacitor - polarized"))
    )
    (comp (ref "C461")
      (value "22uF")
      (footprint "CAPMP3216X180N")
      (description "Polarised capacitor")
      (fields
        (field (name "MANUFACTURER PART NUMBER") "CTE3216-18_22UF_6.3V_10%_LESR0900")
        (field (name "MANUFACTURER") "GENERIC")
        (field (name "AUTHOR") "CERN DEM JLC")
      )
      (libsource (lib "Capacitors") (part "Capacitor - polarized"))
    )
    (comp (ref "C462")
      (value "22uF")
      (footprint "CAPMP3216X180N")
      (description "Polarised capacitor")
      (fields
        (field (name "MANUFACTURER PART NUMBER") "CTE3216-18_22UF_6.3V_10%_LESR0900")
        (field (name "MANUFACTURER") "GENERIC")
        (field (name "AUTHOR") "CERN DEM JLC")
      )
      (libsource (lib "Capacitors") (part "Capacitor - polarized"))
    )
    (comp (ref "C476")
      (value "4.7nF")
      (footprint "CAPCAF50P127X203X55-8N")
      (description "IDC (InterDigitated Capacitors) Low Inductance Capacitors")
      (fields
        (field (name "MANUFACTURER PART NUMBER") "W2L16C473MAT1S")
        (field (name "MANUFACTURER") "AVX")
        (field (name "AUTHOR") "CERN DEM JLC")
      )
      (libsource (lib "Capacitors") (part "Capacitor AVX W2L"))
    )
    (comp (ref "C477")
      (value "4.7nF")
      (footprint "CAPCAF50P127X203X55-8N")
      (description "IDC (InterDigitated Capacitors) Low Inductance Capacitors")
      (fields
        (field (name "MANUFACTURER PART NUMBER") "W2L16C473MAT1S")
        (field (name "MANUFACTURER") "AVX")
        (field (name "AUTHOR") "CERN DEM JLC")
      )
      (libsource (lib "Capacitors") (part "Capacitor AVX W2L"))
    )
    (comp (ref "C478")
      (value "4.7nF")
      (footprint "CAPCAF50P127X203X55-8N")
      (description "IDC (InterDigitated Capacitors) Low Inductance Capacitors")
      (fields
        (field (name "MANUFACTURER PART NUMBER") "W2L16C473MAT1S")
        (field (name "MANUFACTURER") "AVX")
        (field (name "AUTHOR") "CERN DEM JLC")
      )
      (libsource (lib "Capacitors") (part "Capacitor AVX W2L"))
    )
    (comp (ref "C479")
      (value "4.7nF")
      (footprint "CAPCAF50P127X203X55-8N")
      (description "IDC (InterDigitated Capacitors) Low Inductance Capacitors")
      (fields
        (field (name "MANUFACTURER PART NUMBER") "W2L16C473MAT1S")
        (field (name "MANUFACTURER") "AVX")
        (field (name "AUTHOR") "CERN DEM JLC")
      )
      (libsource (lib "Capacitors") (part "Capacitor AVX W2L"))
    )
    (comp (ref "C480")
      (value "4.7nF")
      (footprint "CAPCAF50P127X203X55-8N")
      (description "IDC (InterDigitated Capacitors) Low Inductance Capacitors")
      (fields
        (field (name "MANUFACTURER PART NUMBER") "W2L16C473MAT1S")
        (field (name "MANUFACTURER") "AVX")
        (field (name "AUTHOR") "CERN DEM JLC")
      )
      (libsource (lib "Capacitors") (part "Capacitor AVX W2L"))
    )
    (comp (ref "C481")
      (value "4.7nF")
      (footprint "CAPCAF50P127X203X55-8N")
      (description "IDC (InterDigitated Capacitors) Low Inductance Capacitors")
      (fields
        (field (name "MANUFACTURER PART NUMBER") "W2L16C473MAT1S")
        (field (name "MANUFACTURER") "AVX")
        (field (name "AUTHOR") "CERN DEM JLC")
      )
      (libsource (lib "Capacitors") (part "Capacitor AVX W2L"))
    )
    (comp (ref "C488")
      (value "47uF")
      (footprint "CAPMP6032X280N")
      (description "Polarised capacitor")
      (fields
        (field (name "MANUFACTURER PART NUMBER") "CTE6032-28_47UF_16V_10%_LESR0350")
        (field (name "MANUFACTURER") "GENERIC")
        (field (name "AUTHOR") "CERN DEM JLC")
      )
      (libsource (lib "Capacitors") (part "Capacitor - polarized"))
    )
    (comp (ref "C489")
      (value "47uF")
      (footprint "CAPMP6032X280N")
      (description "Polarised capacitor")
      (fields
        (field (name "MANUFACTURER PART NUMBER") "CTE6032-28_47UF_16V_10%_LESR0350")
        (field (name "MANUFACTURER") "GENERIC")
        (field (name "AUTHOR") "CERN DEM JLC")
      )
      (libsource (lib "Capacitors") (part "Capacitor - polarized"))
    )
    (comp (ref "C490")
      (value "47uF")
      (footprint "CAPMP6032X280N")
      (description "Polarised capacitor")
      (fields
        (field (name "MANUFACTURER PART NUMBER") "CTE6032-28_47UF_16V_10%_LESR0350")
        (field (name "MANUFACTURER") "GENERIC")
        (field (name "AUTHOR") "CERN DEM JLC")
      )
      (libsource (lib "Capacitors") (part "Capacitor - polarized"))
    )
    (comp (ref "C491")
      (value "47uF")
      (footprint "CAPMP6032X280N")
      (description "Polarised capacitor")
      (fields
        (field (name "MANUFACTURER PART NUMBER") "CTE6032-28_47UF_16V_10%_LESR0350")
        (field (name "MANUFACTURER") "GENERIC")
        (field (name "AUTHOR") "CERN DEM JLC")
      )
      (libsource (lib "Capacitors") (part "Capacitor - polarized"))
    )
    (comp (ref "C492")
      (value "47uF")
      (footprint "CAPMP6032X280N")
      (description "Polarised capacitor")
      (fields
        (field (name "MANUFACTURER PART NUMBER") "CTE6032-28_47UF_16V_10%_LESR0350")
        (field (name "MANUFACTURER") "GENERIC")
        (field (name "AUTHOR") "CERN DEM JLC")
      )
      (libsource (lib "Capacitors") (part "Capacitor - polarized"))
    )
    (comp (ref "C493")
      (value "47uF")
      (footprint "CAPMP6032X280N")
      (description "Polarised capacitor")
      (fields
        (field (name "MANUFACTURER PART NUMBER") "CTE6032-28_47UF_16V_10%_LESR0350")
        (field (name "MANUFACTURER") "GENERIC")
        (field (name "AUTHOR") "CERN DEM JLC")
      )
      (libsource (lib "Capacitors") (part "Capacitor - polarized"))
    )
    (comp (ref "HS1")
      (value "17x17x2mm Heat Sink")
      (footprint "HSINK_17x17x2mm")
      (fields
        (field (name "PART NUMBER") "HSINK_17x17x2")
        (field (name "MANUFACTURER") "MoreSuns")
        (field (name "MANUFACTURER PART NUMBER") "17x17x2mm aluminium heat sink")
        (field (name "AUTHOR") "GK")
      )
      (libsource (lib "LIBRARY_SCH") (part "Heat_sink_17x17x2mm"))
    )
    (comp (ref "IC5")
      (value "AD9154BCPZ")
      (footprint "QFN50P1200X1200X90-89N-S755")
      (description "Quad, 16-Bit, 2.4 GSPS, TxDAC+® Digital-to-Analog Converter")
      (fields (field (name "MANUFACTURER") "ANALOG DEVICES") (field (name "AUTHOR") "CERN DEM MR"))
      (libsource (lib "ICs And Semiconductors") (part "AD9154"))
    )
    (comp (ref "IC7")
      (value "LT3045EDD#PBF")
      (footprint "SON50P300X300X80-11N-R175X248")
      (description "20V, 500mA, Ultralow Noise, Ultrahigh PSRR Linear Regulator")
      (fields (field (name "MANUFACTURER") "LINEAR TECHNOLOGY") (field (name "AUTHOR") "CERN DEM JLC"))
      (libsource (lib "ICs And Semiconductors") (part "LT3045EDD"))
    )
    (comp (ref "IC8")
      (value "LT3045EDD#PBF")
      (footprint "SON50P300X300X80-11N-R175X248")
      (description "20V, 500mA, Ultralow Noise, Ultrahigh PSRR Linear Regulator")
      (fields (field (name "MANUFACTURER") "LINEAR TECHNOLOGY") (field (name "AUTHOR") "CERN DEM JLC"))
      (libsource (lib "ICs And Semiconductors") (part "LT3045EDD"))
    )
    (comp (ref "IC9")
      (value "LT3045EDD#PBF")
      (footprint "SON50P300X300X80-11N-R175X248")
      (description "20V, 500mA, Ultralow Noise, Ultrahigh PSRR Linear Regulator")
      (fields (field (name "MANUFACTURER") "LINEAR TECHNOLOGY") (field (name "AUTHOR") "CERN DEM JLC"))
      (libsource (lib "ICs And Semiconductors") (part "LT3045EDD"))
    )
    (comp (ref "IC10")
      (value "LT3045EDD#PBF")
      (footprint "SON50P300X300X80-11N-R175X248")
      (description "20V, 500mA, Ultralow Noise, Ultrahigh PSRR Linear Regulator")
      (fields (field (name "MANUFACTURER") "LINEAR TECHNOLOGY") (field (name "AUTHOR") "CERN DEM JLC"))
      (libsource (lib "ICs And Semiconductors") (part "LT3045EDD"))
    )
    (comp (ref "IC11")
      (value "LT3045EDD#PBF")
      (footprint "SON50P300X300X80-11N-R175X248")
      (description "20V, 500mA, Ultralow Noise, Ultrahigh PSRR Linear Regulator")
      (fields (field (name "MANUFACTURER") "LINEAR TECHNOLOGY") (field (name "AUTHOR") "CERN DEM JLC"))
      (libsource (lib "ICs And Semiconductors") (part "LT3045EDD"))
    )
    (comp (ref "IC12")
      (value "LT3045EDD#PBF")
      (footprint "SON50P300X300X80-11N-R175X248")
      (description "20V, 500mA, Ultralow Noise, Ultrahigh PSRR Linear Regulator")
      (fields (field (name "MANUFACTURER") "LINEAR TECHNOLOGY") (field (name "AUTHOR") "CERN DEM JLC"))
      (libsource (lib "ICs And Semiconductors") (part "LT3045EDD"))
    )
    (comp (ref "IC13")
      (value "LT3045EDD#PBF")
      (footprint "SON50P300X300X80-11N-R175X248")
      (description "20V, 500mA, Ultralow Noise, Ultrahigh PSRR Linear Regulator")
      (fields (field (name "MANUFACTURER") "LINEAR TECHNOLOGY") (field (name "AUTHOR") "CERN DEM JLC"))
      (libsource (lib "ICs And Semiconductors") (part "LT3045EDD"))
    )
    (comp (ref "L14")
      (value "120R@100MHz")
      (footprint "INDC1608X95N")
      (fields
        (field (name "MANUFACTURER PART NUMBER") "BLM18PG121SN1D")
        (field (name "MANUFACTURER") "MURATA")
        (field (name "PART NUMBER") "IND0603_MURATA_BLM18PG121SN1D")
        (field (name "AUTHOR") "CERN DEM BC")
      )
      (libsource (lib "Inductors & Transformers") (part "Ferrite Bead"))
    )
    (comp (ref "L30")
      (value "30R@100MHz")
      (footprint "INDC1608X95N")
      (fields
        (field (name "MANUFACTURER PART NUMBER") "BLM18PG300SN1D")
        (field (name "MANUFACTURER") "MURATA")
        (field (name "PART NUMBER") "IND0603_MURATA_BLM18PG300SN1D")
        (field (name "AUTHOR") "CERN DEM JMW")
      )
      (libsource (lib "Inductors & Transformers") (part "Ferrite Bead"))
    )
    (comp (ref "L31")
      (value "30R@100MHz")
      (footprint "INDC1608X95N")
      (fields
        (field (name "MANUFACTURER PART NUMBER") "BLM18PG300SN1D")
        (field (name "MANUFACTURER") "MURATA")
        (field (name "PART NUMBER") "IND0603_MURATA_BLM18PG300SN1D")
        (field (name "AUTHOR") "CERN DEM JMW")
      )
      (libsource (lib "Inductors & Transformers") (part "Ferrite Bead"))
    )
    (comp (ref "R28")
      (value "1")
      (footprint "RESC1005X40N")
      (description "Resistor - 1%")
      (fields
        (field (name "MANUFACTURER PART NUMBER") "R0402_1R_1%_0.0625W_200PPM")
        (field (name "MANUFACTURER") "GENERIC")
        (field (name "AUTHOR") "CERN DEM JLC")
      )
      (libsource (lib "Resistors") (part "Resistor - 1%"))
    )
    (comp (ref "R29")
      (value "1")
      (footprint "RESC1005X40N")
      (description "Resistor - 1%")
      (fields
        (field (name "MANUFACTURER PART NUMBER") "R0402_1R_1%_0.0625W_200PPM")
        (field (name "MANUFACTURER") "GENERIC")
        (field (name "AUTHOR") "CERN DEM JLC")
      )
      (libsource (lib "Resistors") (part "Resistor - 1%"))
    )
    (comp (ref "R30")
      (value "0")
      (footprint "RESC1005X40N")
      (description "Resistor")
      (fields
        (field (name "MANUFACTURER PART NUMBER") "R0402_0R_JUMPER")
        (field (name "MANUFACTURER") "GENERIC")
        (field (name "AUTHOR") "CERN DEM JLC")
      )
      (libsource (lib "Resistors") (part "Resistor"))
    )
    (comp (ref "R187")
      (value "4k02")
      (footprint "RESC1608X55N")
      (description "Resistor - 0.1%")
      (fields
        (field (name "MANUFACTURER PART NUMBER") "R0603_4K02_0.1%_0.063W_10PPM")
        (field (name "MANUFACTURER") "GENERIC")
        (field (name "AUTHOR") "CERN DEM JLC")
      )
      (libsource (lib "Resistors") (part "Resistor - 0.1%"))
    )
    (comp (ref "R188")
      (value "33k2")
      (footprint "RESC1608X55N")
      (description "Resistor - 0.1%")
      (fields
        (field (name "MANUFACTURER PART NUMBER") "R0603_33K2_0.1%_0.063W_10PPM")
        (field (name "MANUFACTURER") "GENERIC")
        (field (name "AUTHOR") "CERN DEM JLC")
      )
      (libsource (lib "Resistors") (part "Resistor - 0.1%"))
    )
    (comp (ref "R189")
      (value "13k")
      (footprint "RESC1608X55N")
      (description "Resistor - 0.1%")
      (fields
        (field (name "MANUFACTURER PART NUMBER") "R0603_13K_0.1%_0.063W_10PPM")
        (field (name "MANUFACTURER") "GENERIC")
        (field (name "AUTHOR") "CERN DEM JLC")
      )
      (libsource (lib "Resistors") (part "Resistor - 0.1%"))
    )
    (comp (ref "R190")
      (value "13k")
      (footprint "RESC1608X55N")
      (description "Resistor - 0.1%")
      (fields
        (field (name "MANUFACTURER PART NUMBER") "R0603_13K_0.1%_0.063W_10PPM")
        (field (name "MANUFACTURER") "GENERIC")
        (field (name "AUTHOR") "CERN DEM JLC")
      )
      (libsource (lib "Resistors") (part "Resistor - 0.1%"))
    )
    (comp (ref "R191")
      (value "13k")
      (footprint "RESC1608X55N")
      (description "Resistor - 0.1%")
      (fields
        (field (name "MANUFACTURER PART NUMBER") "R0603_13K_0.1%_0.063W_10PPM")
        (field (name "MANUFACTURER") "GENERIC")
        (field (name "AUTHOR") "CERN DEM JLC")
      )
      (libsource (lib "Resistors") (part "Resistor - 0.1%"))
    )
    (comp (ref "R192")
      (value "13k")
      (footprint "RESC1608X55N")
      (description "Resistor - 0.1%")
      (fields
        (field (name "MANUFACTURER PART NUMBER") "R0603_13K_0.1%_0.063W_10PPM")
        (field (name "MANUFACTURER") "GENERIC")
        (field (name "AUTHOR") "CERN DEM JLC")
      )
      (libsource (lib "Resistors") (part "Resistor - 0.1%"))
    )
    (comp (ref "R193")
      (value "13k")
      (footprint "RESC1608X55N")
      (description "Resistor - 0.1%")
      (fields
        (field (name "MANUFACTURER PART NUMBER") "R0603_13K_0.1%_0.063W_10PPM")
        (field (name "MANUFACTURER") "GENERIC")
        (field (name "AUTHOR") "CERN DEM JLC")
      )
      (libsource (lib "Resistors") (part "Resistor - 0.1%"))
    )
    (comp (ref "R194")
      (value "13k")
      (footprint "RESC1608X55N")
      (description "Resistor - 0.1%")
      (fields
        (field (name "MANUFACTURER PART NUMBER") "R0603_13K_0.1%_0.063W_10PPM")
        (field (name "MANUFACTURER") "GENERIC")
        (field (name "AUTHOR") "CERN DEM JLC")
      )
      (libsource (lib "Resistors") (part "Resistor - 0.1%"))
    )
    (comp (ref "R217")
      (value "0R02")
      (footprint "RESC3216X80N")
      (description "Resistor - 1%")
      (fields
        (field (name "MANUFACTURER PART NUMBER") "LRF1206-R020FI")
        (field (name "MANUFACTURER") "TT Electronics")
        (field (name "AUTHOR") "CERN DEM JLC")
      )
      (libsource (lib "Resistors") (part "Resistor - 1%"))
    )
    (comp (ref "R218")
      (value "0R02")
      (footprint "RESC3216X80N")
      (description "Resistor - 1%")
      (fields
        (field (name "MANUFACTURER PART NUMBER") "LRF1206-R020FI")
        (field (name "MANUFACTURER") "TT Electronics")
        (field (name "AUTHOR") "CERN DEM JLC")
      )
      (libsource (lib "Resistors") (part "Resistor - 1%"))
    )
    (comp (ref "R223")
      (value "49R9")
      (footprint "RESC0603X28N")
      (description "49R9k, 0201, 1%")
      (fields
        (field (name "MANUFACTURER PART NUMBER") "R0201_49R9_1%_0.05W_200PPM")
        (field (name "MANUFACTURER") "GENERIC")
        (field (name "AUTHOR") "GK")
      )
      (libsource (lib "LIBRARY_SCH") (part "RES_0201_1k_49R9"))
    )
    (comp (ref "R224")
      (value "49R9")
      (footprint "RESC0603X28N")
      (description "49R9k, 0201, 1%")
      (fields
        (field (name "MANUFACTURER PART NUMBER") "R0201_49R9_1%_0.05W_200PPM")
        (field (name "MANUFACTURER") "GENERIC")
        (field (name "AUTHOR") "GK")
      )
      (libsource (lib "LIBRARY_SCH") (part "RES_0201_1k_49R9"))
    )
    (comp (ref "R225")
      (value "49R9")
      (footprint "RESC0603X28N")
      (description "49R9k, 0201, 1%")
      (fields
        (field (name "MANUFACTURER PART NUMBER") "R0201_49R9_1%_0.05W_200PPM")
        (field (name "MANUFACTURER") "GENERIC")
        (field (name "AUTHOR") "GK")
      )
      (libsource (lib "LIBRARY_SCH") (part "RES_0201_1k_49R9"))
    )
    (comp (ref "R226")
      (value "49R9")
      (footprint "RESC0603X28N")
      (description "49R9k, 0201, 1%")
      (fields
        (field (name "MANUFACTURER PART NUMBER") "R0201_49R9_1%_0.05W_200PPM")
        (field (name "MANUFACTURER") "GENERIC")
        (field (name "AUTHOR") "GK")
      )
      (libsource (lib "LIBRARY_SCH") (part "RES_0201_1k_49R9"))
    )
    (comp (ref "R227")
      (value "49R9")
      (footprint "RESC0603X28N")
      (description "49R9k, 0201, 1%")
      (fields
        (field (name "MANUFACTURER PART NUMBER") "R0201_49R9_1%_0.05W_200PPM")
        (field (name "MANUFACTURER") "GENERIC")
        (field (name "AUTHOR") "GK")
      )
      (libsource (lib "LIBRARY_SCH") (part "RES_0201_1k_49R9"))
    )
    (comp (ref "R228")
      (value "49R9")
      (footprint "RESC0603X28N")
      (description "49R9k, 0201, 1%")
      (fields
        (field (name "MANUFACTURER PART NUMBER") "R0201_49R9_1%_0.05W_200PPM")
        (field (name "MANUFACTURER") "GENERIC")
        (field (name "AUTHOR") "GK")
      )
      (libsource (lib "LIBRARY_SCH") (part "RES_0201_1k_49R9"))
    )
    (comp (ref "R229")
      (value "49R9")
      (footprint "RESC0603X28N")
      (description "49R9k, 0201, 1%")
      (fields
        (field (name "MANUFACTURER PART NUMBER") "R0201_49R9_1%_0.05W_200PPM")
        (field (name "MANUFACTURER") "GENERIC")
        (field (name "AUTHOR") "GK")
      )
      (libsource (lib "LIBRARY_SCH") (part "RES_0201_1k_49R9"))
    )
    (comp (ref "R230")
      (value "49R9")
      (footprint "RESC0603X28N")
      (description "49R9k, 0201, 1%")
      (fields
        (field (name "MANUFACTURER PART NUMBER") "R0201_49R9_1%_0.05W_200PPM")
        (field (name "MANUFACTURER") "GENERIC")
        (field (name "AUTHOR") "GK")
      )
      (libsource (lib "LIBRARY_SCH") (part "RES_0201_1k_49R9"))
    )
    (comp (ref "R231")
      (value "100")
      (footprint "RESC0603X28N")
      (description "Resistor - 1%")
      (fields
        (field (name "MANUFACTURER PART NUMBER") "R0201_100R_1%_0.05W_200PPM")
        (field (name "MANUFACTURER") "GENERIC")
        (field (name "AUTHOR") "CERN DEM JLC")
      )
      (libsource (lib "Resistors") (part "Resistor - 1%"))
    )
    (comp (ref "R232")
      (value "100")
      (footprint "RESC0603X28N")
      (description "Resistor - 1%")
      (fields
        (field (name "MANUFACTURER PART NUMBER") "R0201_100R_1%_0.05W_200PPM")
        (field (name "MANUFACTURER") "GENERIC")
        (field (name "AUTHOR") "CERN DEM JLC")
      )
      (libsource (lib "Resistors") (part "Resistor - 1%"))
    )
    (comp (ref "TP63")
      (value "Test Point")
      (footprint "TPS127")
      (fields (field (name "PART NUMBER") "SMD_PAD_1.27X1.27MM") (field (name "AUTHOR") "CERN DEM JLC"))
      (libsource (lib "Eletro-mechanical") (part "Test Point"))
    )
    (comp (ref "TP64")
      (value "Test Point")
      (footprint "TPS127")
      (fields (field (name "PART NUMBER") "SMD_PAD_1.27X1.27MM") (field (name "AUTHOR") "CERN DEM JLC"))
      (libsource (lib "Eletro-mechanical") (part "Test Point"))
    )
    (comp (ref "TP65")
      (value "Test Point")
      (footprint "TPS127")
      (fields (field (name "PART NUMBER") "SMD_PAD_1.27X1.27MM") (field (name "AUTHOR") "CERN DEM JLC"))
      (libsource (lib "Eletro-mechanical") (part "Test Point"))
    )
    (comp (ref "TP66")
      (value "Test Point")
      (footprint "TPS127")
      (fields (field (name "PART NUMBER") "SMD_PAD_1.27X1.27MM") (field (name "AUTHOR") "CERN DEM JLC"))
      (libsource (lib "Eletro-mechanical") (part "Test Point"))
    )
    (comp (ref "TP67")
      (value "Test Point")
      (footprint "TPS127")
      (fields (field (name "PART NUMBER") "SMD_PAD_1.27X1.27MM") (field (name "AUTHOR") "CERN DEM JLC"))
      (libsource (lib "Eletro-mechanical") (part "Test Point"))
    )
    (comp (ref "TP68")
      (value "Test Point")
      (footprint "TPS127")
      (fields (field (name "PART NUMBER") "SMD_PAD_1.27X1.27MM") (field (name "AUTHOR") "CERN DEM JLC"))
      (libsource (lib "Eletro-mechanical") (part "Test Point"))
    )
    (comp (ref "TP69")
      (value "Test Point")
      (footprint "TPS127")
      (fields (field (name "PART NUMBER") "SMD_PAD_1.27X1.27MM") (field (name "AUTHOR") "CERN DEM JLC"))
      (libsource (lib "Eletro-mechanical") (part "Test Point"))
    )
    (comp (ref "TP70")
      (value "Test Point")
      (footprint "TPS127")
      (fields (field (name "PART NUMBER") "SMD_PAD_1.27X1.27MM") (field (name "AUTHOR") "CERN DEM JLC"))
      (libsource (lib "Eletro-mechanical") (part "Test Point"))
    )
    (comp (ref "TP71")
      (value "Test Point")
      (footprint "TPS127")
      (fields (field (name "PART NUMBER") "SMD_PAD_1.27X1.27MM") (field (name "AUTHOR") "CERN DEM JLC"))
      (libsource (lib "Eletro-mechanical") (part "Test Point"))
    )
    (comp (ref "TP72")
      (value "Test Point")
      (footprint "TPS127")
      (fields (field (name "PART NUMBER") "SMD_PAD_1.27X1.27MM") (field (name "AUTHOR") "CERN DEM JLC"))
      (libsource (lib "Eletro-mechanical") (part "Test Point"))
    )
  )
  (nets
    (net (code "3") (name "/AVDD33") (class "Default")
      (node (ref "C25") (pin "2") (pinfunction "2_2") (pintype "passive"))
      (node (ref "C26") (pin "2") (pinfunction "2_2") (pintype "passive"))
      (node (ref "C27") (pin "2") (pinfunction "2_2") (pintype "passive"))
      (node (ref "C28") (pin "2") (pinfunction "2_2") (pintype "passive"))
      (node (ref "C29") (pin "2") (pinfunction "2_2") (pintype "passive"))
      (node (ref "C30") (pin "2") (pinfunction "2_2") (pintype "passive"))
      (node (ref "C476") (pin "1") (pinfunction "1_1") (pintype "passive"))
      (node (ref "C476") (pin "3") (pinfunction "3_3") (pintype "passive"))
      (node (ref "C476") (pin "5") (pinfunction "5_5") (pintype "passive"))
      (node (ref "C476") (pin "7") (pinfunction "7_7") (pintype "passive"))
      (node (ref "C76") (pin "2") (pinfunction "2_2") (pintype "passive"))
      (node (ref "C97") (pin "1") (pinfunction "1_1") (pintype "passive"))
      (node (ref "IC5") (pin "67") (pinfunction "AVDD33_67") (pintype "power_in"))
      (node (ref "IC5") (pin "70") (pinfunction "AVDD33_70") (pintype "power_in"))
      (node (ref "IC5") (pin "72") (pinfunction "AVDD33_72") (pintype "power_in"))
      (node (ref "IC5") (pin "75") (pinfunction "AVDD33_75") (pintype "power_in"))
      (node (ref "IC5") (pin "77") (pinfunction "AVDD33_77") (pintype "power_in"))
      (node (ref "IC5") (pin "80") (pinfunction "AVDD33_80") (pintype "power_in"))
      (node (ref "IC5") (pin "82") (pinfunction "AVDD33_82") (pintype "power_in"))
      (node (ref "IC5") (pin "85") (pinfunction "AVDD33_85") (pintype "power_in"))
      (node (ref "L31") (pin "2") (pinfunction "2_2") (pintype "passive"))
      (node (ref "R223") (pin "2") (pinfunction "2_2") (pintype "passive"))
      (node (ref "R224") (pin "2") (pinfunction "2_2") (pintype "passive"))
      (node (ref "R225") (pin "2") (pinfunction "2_2") (pintype "passive"))
      (node (ref "R226") (pin "2") (pinfunction "2_2") (pintype "passive"))
      (node (ref "R227") (pin "2") (pinfunction "2_2") (pintype "passive"))
      (node (ref "R228") (pin "2") (pinfunction "2_2") (pintype "passive"))
      (node (ref "R229") (pin "2") (pinfunction "2_2") (pintype "passive"))
      (node (ref "R230") (pin "2") (pinfunction "2_2") (pintype "passive"))
    )
    (net (code "4") (name "/CVDD12") (class "Default")
      (node (ref "C312") (pin "2") (pinfunction "2_2") (pintype "passive"))
      (node (ref "C362") (pin "1") (pinfunction "1_1") (pintype "passive"))
      (node (ref "C477") (pin "1") (pinfunction "1_1") (pintype "passive"))
      (node (ref "C477") (pin "3") (pinfunction "3_3") (pintype "passive"))
      (node (ref "C477") (pin "5") (pinfunction "5_5") (pintype "passive"))
      (node (ref "C477") (pin "7") (pinfunction "7_7") (pintype "passive"))
      (node (ref "C53") (pin "2") (pinfunction "2_2") (pintype "passive"))
      (node (ref "C54") (pin "2") (pinfunction "2_2") (pintype "passive"))
      (node (ref "C55") (pin "2") (pinfunction "2_2") (pintype "passive"))
      (node (ref "C56") (pin "2") (pinfunction "2_2") (pintype "passive"))
      (node (ref "C57") (pin "2") (pinfunction "2_2") (pintype "passive"))
      (node (ref "C58") (pin "2") (pinfunction "2_2") (pintype "passive"))
      (node (ref "C84") (pin "2") (pinfunction "2_2") (pintype "passive"))
      (node (ref "IC12") (pin "10") (pinfunction "OUT_10") (pintype "output"))
      (node (ref "IC12") (pin "9") (pinfunction "OUTS_9") (pintype "output"))
      (node (ref "IC5") (pin "71") (pinfunction "CVDD12_71") (pintype "power_in"))
      (node (ref "IC5") (pin "76") (pinfunction "CVDD12_76") (pintype "power_in"))
      (node (ref "IC5") (pin "81") (pinfunction "CVDD12_81") (pintype "power_in"))
      (node (ref "IC5") (pin "87") (pinfunction "CVDD12_87") (pintype "power_in"))
      (node (ref "TP71") (pin "1") (pinfunction "1_1") (pintype "bidirectional"))
    )
    (net (code "5") (name "/DAC_3V3_LDO") (class "Default")
      (node (ref "C314") (pin "2") (pinfunction "2_2") (pintype "passive"))
      (node (ref "IC13") (pin "10") (pinfunction "OUT_10") (pintype "output"))
      (node (ref "IC13") (pin "9") (pinfunction "OUTS_9") (pintype "output"))
      (node (ref "L30") (pin "1") (pinfunction "1_1") (pintype "passive"))
      (node (ref "L31") (pin "1") (pinfunction "1_1") (pintype "passive"))
      (node (ref "TP67") (pin "1") (pinfunction "1_1") (pintype "bidirectional"))
    )
    (net (code "6") (name "/DAC_CLK_N") (class "Default")
      (node (ref "IC5") (pin "3") (pinfunction "CLK-_3") (pintype "input"))
      (node (ref "R232") (pin "1") (pinfunction "1_1") (pintype "passive"))
    )
    (net (code "7") (name "/DAC_CLK_P") (class "Default")
      (node (ref "IC5") (pin "2") (pinfunction "CLK+_2") (pintype "input"))
      (node (ref "R232") (pin "2") (pinfunction "2_2") (pintype "passive"))
    )
    (net (code "8") (name "/DAC_IRQn") (class "Default")
      (node (ref "IC5") (pin "60") (pinfunction "~{IRQ}_60") (pintype "input"))
    )
    (net (code "9") (name "/DAC_RESETn") (class "Default")
      (node (ref "IC5") (pin "61") (pinfunction "~{RESET}_61") (pintype "input"))
    )
    (net (code "10") (name "/DAC_SPI_CSn") (class "Default")
      (node (ref "IC5") (pin "65") (pinfunction "~{CS}_65") (pintype "input"))
      (node (ref "TP66") (pin "1") (pinfunction "1_1") (pintype "bidirectional"))
    )
    (net (code "11") (name "/DAC_SPI_SCLK") (class "Default")
      (node (ref "IC5") (pin "64") (pinfunction "SCLK_64") (pintype "input"))
      (node (ref "TP65") (pin "1") (pinfunction "1_1") (pintype "bidirectional"))
    )
    (net (code "12") (name "/DAC_SPI_SDIO") (class "Default")
      (node (ref "IC5") (pin "63") (pinfunction "SDIO_63") (pintype "bidirectional"))
      (node (ref "TP64") (pin "1") (pinfunction "1_1") (pintype "bidirectional"))
    )
    (net (code "13") (name "/DAC_SPI_SDO") (class "Default")
      (node (ref "IC5") (pin "62") (pinfunction "SDO_62") (pintype "output"))
      (node (ref "TP63") (pin "1") (pinfunction "1_1") (pintype "bidirectional"))
    )
    (net (code "14") (name "/DAC_SYSREF_N") (class "Default")
      (node (ref "IC5") (pin "6") (pinfunction "SYSREF-_6") (pintype "input"))
      (node (ref "R231") (pin "1") (pinfunction "1_1") (pintype "passive"))
    )
    (net (code "15") (name "/DAC_SYSREF_P") (class "Default")
      (node (ref "IC5") (pin "5") (pinfunction "SYSREF+_5") (pintype "input"))
      (node (ref "R231") (pin "2") (pinfunction "2_2") (pintype "passive"))
    )
    (net (code "16") (name "/DAC_TXEN0") (class "Default")
      (node (ref "IC5") (pin "11") (pinfunction "TXEN0_11") (pintype "input"))
    )
    (net (code "17") (name "/DAC_TXEN1") (class "Default")
      (node (ref "IC5") (pin "12") (pinfunction "TXEN1_12") (pintype "input"))
    )
    (net (code "18") (name "/DVDD12") (class "Default")
      (node (ref "C304") (pin "2") (pinfunction "2_2") (pintype "passive"))
      (node (ref "C363") (pin "1") (pinfunction "1_1") (pintype "passive"))
      (node (ref "C478") (pin "1") (pinfunction "1_1") (pintype "passive"))
      (node (ref "C478") (pin "3") (pinfunction "3_3") (pintype "passive"))
      (node (ref "C478") (pin "5") (pinfunction "5_5") (pintype "passive"))
      (node (ref "C478") (pin "7") (pinfunction "7_7") (pintype "passive"))
      (node (ref "C59") (pin "2") (pinfunction "2_2") (pintype "passive"))
      (node (ref "C60") (pin "2") (pinfunction "2_2") (pintype "passive"))
      (node (ref "C61") (pin "2") (pinfunction "2_2") (pintype "passive"))
      (node (ref "C62") (pin "2") (pinfunction "2_2") (pintype "passive"))
      (node (ref "C63") (pin "2") (pinfunction "2_2") (pintype "passive"))
      (node (ref "C64") (pin "2") (pinfunction "2_2") (pintype "passive"))
      (node (ref "C80") (pin "2") (pinfunction "2_2") (pintype "passive"))
      (node (ref "IC5") (pin "13") (pinfunction "DVDD12_13") (pintype "power_in"))
      (node (ref "IC5") (pin "14") (pinfunction "DVDD12_14") (pintype "power_in"))
      (node (ref "IC5") (pin "53") (pinfunction "DVDD12_53") (pintype "power_in"))
      (node (ref "IC9") (pin "10") (pinfunction "OUT_10") (pintype "output"))
      (node (ref "IC9") (pin "9") (pinfunction "OUTS_9") (pintype "output"))
      (node (ref "TP69") (pin "1") (pinfunction "1_1") (pintype "bidirectional"))
    )
    (net (code "19") (name "/IOVDD") (class "Default")
      (node (ref "C100") (pin "1") (pinfunction "1_1") (pintype "passive"))
      (node (ref "C382") (pin "1") (pinfunction "1_1") (pintype "passive"))
      (node (ref "C493") (pin "1") (pinfunction "1_1") (pintype "passive"))
      (node (ref "C74") (pin "2") (pinfunction "2_2") (pintype "passive"))
      (node (ref "C75") (pin "2") (pinfunction "2_2") (pintype "passive"))
      (node (ref "C78") (pin "2") (pinfunction "2_2") (pintype "passive"))
      (node (ref "IC5") (pin "66") (pinfunction "IOVDD_66") (pintype "power_in"))
      (node (ref "L14") (pin "2") (pinfunction "2_2") (pintype "passive"))
    )
    (net (code "20") (name "/OUT0_N") (class "Default")
      (node (ref "IC5") (pin "83") (pinfunction "OUT0-_83") (pintype "output"))
      (node (ref "R223") (pin "1") (pinfunction "1_1") (pintype "passive"))
    )
    (net (code "21") (name "/OUT0_P") (class "Default")
      (node (ref "IC5") (pin "84") (pinfunction "OUT0+_84") (pintype "output"))
      (node (ref "R224") (pin "1") (pinfunction "1_1") (pintype "passive"))
    )
    (net (code "22") (name "/OUT1_N") (class "Default")
      (node (ref "IC5") (pin "79") (pinfunction "OUT1-_79") (pintype "output"))
      (node (ref "R225") (pin "1") (pinfunction "1_1") (pintype "passive"))
    )
    (net (code "23") (name "/OUT1_P") (class "Default")
      (node (ref "IC5") (pin "78") (pinfunction "OUT1+_78") (pintype "output"))
      (node (ref "R226") (pin "1") (pinfunction "1_1") (pintype "passive"))
    )
    (net (code "24") (name "/OUT2_N") (class "Default")
      (node (ref "IC5") (pin "73") (pinfunction "OUT2-_73") (pintype "output"))
      (node (ref "R227") (pin "1") (pinfunction "1_1") (pintype "passive"))
    )
    (net (code "25") (name "/OUT2_P") (class "Default")
      (node (ref "IC5") (pin "74") (pinfunction "OUT2+_74") (pintype "output"))
      (node (ref "R228") (pin "1") (pinfunction "1_1") (pintype "passive"))
    )
    (net (code "26") (name "/OUT3_N") (class "Default")
      (node (ref "IC5") (pin "69") (pinfunction "OUT3-_69") (pintype "output"))
      (node (ref "R229") (pin "1") (pinfunction "1_1") (pintype "passive"))
    )
    (net (code "27") (name "/OUT3_P") (class "Default")
      (node (ref "IC5") (pin "68") (pinfunction "OUT3+_68") (pintype "output"))
      (node (ref "R230") (pin "1") (pinfunction "1_1") (pintype "passive"))
    )
    (net (code "28") (name "/PLLVDD12") (class "Default")
      (node (ref "C310") (pin "2") (pinfunction "2_2") (pintype "passive"))
      (node (ref "C491") (pin "1") (pinfunction "1_1") (pintype "passive"))
      (node (ref "C69") (pin "2") (pinfunction "2_2") (pintype "passive"))
      (node (ref "C70") (pin "2") (pinfunction "2_2") (pintype "passive"))
      (node (ref "C71") (pin "2") (pinfunction "2_2") (pintype "passive"))
      (node (ref "C83") (pin "2") (pinfunction "2_2") (pintype "passive"))
      (node (ref "C98") (pin "1") (pinfunction "1_1") (pintype "passive"))
      (node (ref "IC11") (pin "10") (pinfunction "OUT_10") (pintype "output"))
      (node (ref "IC11") (pin "9") (pinfunction "OUTS_9") (pintype "output"))
      (node (ref "IC5") (pin "32") (pinfunction "SVDD12_32") (pintype "power_in"))
      (node (ref "IC5") (pin "33") (pinfunction "SVDD12_33") (pintype "power_in"))
      (node (ref "TP72") (pin "1") (pinfunction "1_1") (pintype "bidirectional"))
    )
    (net (code "29") (name "/PVDD12") (class "Default")
      (node (ref "C302") (pin "2") (pinfunction "2_2") (pintype "passive"))
      (node (ref "C31") (pin "2") (pinfunction "2_2") (pintype "passive"))
      (node (ref "C32") (pin "2") (pinfunction "2_2") (pintype "passive"))
      (node (ref "C33") (pin "2") (pinfunction "2_2") (pintype "passive"))
      (node (ref "C34") (pin "2") (pinfunction "2_2") (pintype "passive"))
      (node (ref "C35") (pin "2") (pinfunction "2_2") (pintype "passive"))
      (node (ref "C36") (pin "2") (pinfunction "2_2") (pintype "passive"))
      (node (ref "C37") (pin "2") (pinfunction "2_2") (pintype "passive"))
      (node (ref "C38") (pin "2") (pinfunction "2_2") (pintype "passive"))
      (node (ref "C39") (pin "2") (pinfunction "2_2") (pintype "passive"))
      (node (ref "C40") (pin "2") (pinfunction "2_2") (pintype "passive"))
      (node (ref "C41") (pin "2") (pinfunction "2_2") (pintype "passive"))
      (node (ref "C479") (pin "1") (pinfunction "1_1") (pintype "passive"))
      (node (ref "C479") (pin "3") (pinfunction "3_3") (pintype "passive"))
      (node (ref "C479") (pin "5") (pinfunction "5_5") (pintype "passive"))
      (node (ref "C479") (pin "7") (pinfunction "7_7") (pintype "passive"))
      (node (ref "C488") (pin "1") (pinfunction "1_1") (pintype "passive"))
      (node (ref "C79") (pin "2") (pinfunction "2_2") (pintype "passive"))
      (node (ref "C96") (pin "1") (pinfunction "1_1") (pintype "passive"))
      (node (ref "IC5") (pin "1") (pinfunction "PVDD12_1") (pintype "power_in"))
      (node (ref "IC5") (pin "10") (pinfunction "PVDD12_10") (pintype "power_in"))
      (node (ref "IC5") (pin "4") (pinfunction "PVDD12_4") (pintype "power_in"))
      (node (ref "IC5") (pin "56") (pinfunction "PVDD12_56") (pintype "power_in"))
      (node (ref "IC5") (pin "57") (pinfunction "PVDD12_57") (pintype "power_in"))
      (node (ref "IC5") (pin "7") (pinfunction "PVDD12_7") (pintype "power_in"))
      (node (ref "IC5") (pin "8") (pinfunction "PVDD12_8") (pintype "power_in"))
      (node (ref "IC5") (pin "9") (pinfunction "PVDD12_9") (pintype "power_in"))
      (node (ref "IC8") (pin "10") (pinfunction "OUT_10") (pintype "output"))
      (node (ref "IC8") (pin "9") (pinfunction "OUTS_9") (pintype "output"))
      (node (ref "TP68") (pin "1") (pinfunction "1_1") (pintype "bidirectional"))
    )
    (net (code "30") (name "/SERDIN0_N") (class "Default")
      (node (ref "IC5") (pin "16") (pinfunction "SERDIN0-_16") (pintype "input"))
    )
    (net (code "31") (name "/SERDIN0_P") (class "Default")
      (node (ref "IC5") (pin "15") (pinfunction "SERDIN0+_15") (pintype "input"))
    )
    (net (code "32") (name "/SERDIN1_N") (class "Default")
      (node (ref "IC5") (pin "19") (pinfunction "SERDIN1-_19") (pintype "input"))
    )
    (net (code "33") (name "/SERDIN1_P") (class "Default")
      (node (ref "IC5") (pin "18") (pinfunction "SERDIN1+_18") (pintype "input"))
    )
    (net (code "34") (name "/SERDIN2_N") (class "Default")
      (node (ref "IC5") (pin "27") (pinfunction "SERDIN2-_27") (pintype "input"))
    )
    (net (code "35") (name "/SERDIN2_P") (class "Default")
      (node (ref "IC5") (pin "26") (pinfunction "SERDIN2+_26") (pintype "input"))
    )
    (net (code "36") (name "/SERDIN3_N") (class "Default")
      (node (ref "IC5") (pin "30") (pinfunction "SERDIN3-_30") (pintype "input"))
    )
    (net (code "37") (name "/SERDIN3_P") (class "Default")
      (node (ref "IC5") (pin "29") (pinfunction "SERDIN3+_29") (pintype "input"))
    )
    (net (code "38") (name "/SERDIN4_N") (class "Default")
      (node (ref "IC5") (pin "37") (pinfunction "SERDIN4-_37") (pintype "input"))
    )
    (net (code "39") (name "/SERDIN4_P") (class "Default")
      (node (ref "IC5") (pin "38") (pinfunction "SERDIN4+_38") (pintype "input"))
    )
    (net (code "40") (name "/SERDIN5_N") (class "Default")
      (node (ref "IC5") (pin "40") (pinfunction "SERDIN5-_40") (pintype "input"))
    )
    (net (code "41") (name "/SERDIN5_P") (class "Default")
      (node (ref "IC5") (pin "41") (pinfunction "SERDIN5+_41") (pintype "input"))
    )
    (net (code "42") (name "/SERDIN6_N") (class "Default")
      (node (ref "IC5") (pin "48") (pinfunction "SERDIN6-_48") (pintype "input"))
    )
    (net (code "43") (name "/SERDIN6_P") (class "Default")
      (node (ref "IC5") (pin "49") (pinfunction "SERDIN6+_49") (pintype "input"))
    )
    (net (code "44") (name "/SERDIN7_N") (class "Default")
      (node (ref "IC5") (pin "51") (pinfunction "SERDIN7-_51") (pintype "input"))
    )
    (net (code "45") (name "/SERDIN7_P") (class "Default")
      (node (ref "IC5") (pin "52") (pinfunction "SERDIN7+_52") (pintype "input"))
    )
    (net (code "46") (name "/SIOVDD33") (class "Default")
      (node (ref "C492") (pin "1") (pinfunction "1_1") (pintype "passive"))
      (node (ref "C72") (pin "2") (pinfunction "2_2") (pintype "passive"))
      (node (ref "C73") (pin "2") (pinfunction "2_2") (pintype "passive"))
      (node (ref "C77") (pin "2") (pinfunction "2_2") (pintype "passive"))
      (node (ref "C99") (pin "1") (pinfunction "1_1") (pintype "passive"))
      (node (ref "IC5") (pin "35") (pinfunction "SIOVDD33_35") (pintype "power_in"))
      (node (ref "L30") (pin "2") (pinfunction "2_2") (pintype "passive"))
    )
    (net (code "47") (name "/SVDD12") (class "Default")
      (node (ref "C361") (pin "1") (pinfunction "1_1") (pintype "passive"))
      (node (ref "C364") (pin "1") (pinfunction "1_1") (pintype "passive"))
      (node (ref "C42") (pin "2") (pinfunction "2_2") (pintype "passive"))
      (node (ref "C43") (pin "2") (pinfunction "2_2") (pintype "passive"))
      (node (ref "C44") (pin "2") (pinfunction "2_2") (pintype "passive"))
      (node (ref "C45") (pin "2") (pinfunction "2_2") (pintype "passive"))
      (node (ref "C46") (pin "2") (pinfunction "2_2") (pintype "passive"))
      (node (ref "C47") (pin "2") (pinfunction "2_2") (pintype "passive"))
      (node (ref "C48") (pin "2") (pinfunction "2_2") (pintype "passive"))
      (node (ref "C480") (pin "1") (pinfunction "1_1") (pintype "passive"))
      (node (ref "C480") (pin "3") (pinfunction "3_3") (pintype "passive"))
      (node (ref "C480") (pin "5") (pinfunction "5_5") (pintype "passive"))
      (node (ref "C480") (pin "7") (pinfunction "7_7") (pintype "passive"))
      (node (ref "C481") (pin "1") (pinfunction "1_1") (pintype "passive"))
      (node (ref "C481") (pin "3") (pinfunction "3_3") (pintype "passive"))
      (node (ref "C481") (pin "5") (pinfunction "5_5") (pintype "passive"))
      (node (ref "C481") (pin "7") (pinfunction "7_7") (pintype "passive"))
      (node (ref "C489") (pin "1") (pinfunction "1_1") (pintype "passive"))
      (node (ref "C49") (pin "2") (pinfunction "2_2") (pintype "passive"))
      (node (ref "C490") (pin "1") (pinfunction "1_1") (pintype "passive"))
      (node (ref "C50") (pin "2") (pinfunction "2_2") (pintype "passive"))
      (node (ref "C51") (pin "2") (pinfunction "2_2") (pintype "passive"))
      (node (ref "C52") (pin "2") (pinfunction "2_2") (pintype "passive"))
      (node (ref "C65") (pin "2") (pinfunction "2_2") (pintype "passive"))
      (node (ref "C66") (pin "2") (pinfunction "2_2") (pintype "passive"))
      (node (ref "C67") (pin "2") (pinfunction "2_2") (pintype "passive"))
      (node (ref "C68") (pin "2") (pinfunction "2_2") (pintype "passive"))
      (node (ref "IC5") (pin "17") (pinfunction "SVDD12_17") (pintype "power_in"))
      (node (ref "IC5") (pin "20") (pinfunction "SVDD12_20") (pintype "power_in"))
      (node (ref "IC5") (pin "22") (pinfunction "SVDD12_22") (pintype "power_in"))
      (node (ref "IC5") (pin "28") (pinfunction "SVDD12_28") (pintype "power_in"))
      (node (ref "IC5") (pin "31") (pinfunction "SVDD12_31") (pintype "power_in"))
      (node (ref "IC5") (pin "36") (pinfunction "SVDD12_36") (pintype "power_in"))
      (node (ref "IC5") (pin "39") (pinfunction "SVDD12_39") (pintype "power_in"))
      (node (ref "IC5") (pin "45") (pinfunction "SVDD12_45") (pintype "power_in"))
      (node (ref "IC5") (pin "47") (pinfunction "SVDD12_47") (pintype "power_in"))
      (node (ref "IC5") (pin "50") (pinfunction "SVDD12_50") (pintype "power_in"))
      (node (ref "R217") (pin "2") (pinfunction "2_2") (pintype "passive"))
      (node (ref "R218") (pin "2") (pinfunction "2_2") (pintype "passive"))
      (node (ref "R30") (pin "1") (pinfunction "1_1") (pintype "passive"))
      (node (ref "TP70") (pin "1") (pinfunction "1_1") (pintype "bidirectional"))
    )
    (net (code "48") (name "/SVDD12R1") (class "Default")
      (node (ref "C306") (pin "2") (pinfunction "2_2") (pintype "passive"))
      (node (ref "C81") (pin "2") (pinfunction "2_2") (pintype "passive"))
      (node (ref "IC7") (pin "10") (pinfunction "OUT_10") (pintype "output"))
      (node (ref "IC7") (pin "9") (pinfunction "OUTS_9") (pintype "output"))
      (node (ref "R217") (pin "1") (pinfunction "1_1") (pintype "passive"))
    )
    (net (code "49") (name "/SVDD12R2") (class "Default")
      (node (ref "C308") (pin "2") (pinfunction "2_2") (pintype "passive"))
      (node (ref "C82") (pin "2") (pinfunction "2_2") (pintype "passive"))
      (node (ref "IC10") (pin "10") (pinfunction "OUT_10") (pintype "output"))
      (node (ref "IC10") (pin "9") (pinfunction "OUTS_9") (pintype "output"))
      (node (ref "R218") (pin "1") (pinfunction "1_1") (pintype "passive"))
    )
    (net (code "50") (name "/SYNCOUT0_N") (class "Default")
      (node (ref "IC5") (pin "24") (pinfunction "~{SYNCOUT0-}_24") (pintype "output"))
    )
    (net (code "51") (name "/SYNCOUT0_P") (class "Default")
      (node (ref "IC5") (pin "23") (pinfunction "~{SYNCOUT0+}_23") (pintype "output"))
    )
    (net (code "52") (name "/VTT") (class "Default")
      (node (ref "C21") (pin "2") (pinfunction "2_2") (pintype "passive"))
      (node (ref "C22") (pin "2") (pinfunction "2_2") (pintype "passive"))
      (node (ref "C23") (pin "2") (pinfunction "2_2") (pintype "passive"))
      (node (ref "C24") (pin "2") (pinfunction "2_2") (pintype "passive"))
      (node (ref "C379") (pin "1") (pinfunction "1_1") (pintype "passive"))
      (node (ref "IC5") (pin "21") (pinfunction "VTT_21") (pintype "power_in"))
      (node (ref "IC5") (pin "25") (pinfunction "VTT_25") (pintype "power_in"))
      (node (ref "IC5") (pin "42") (pinfunction "VTT_42") (pintype "power_in"))
      (node (ref "IC5") (pin "46") (pinfunction "VTT_46") (pintype "power_in"))
      (node (ref "R30") (pin "2") (pinfunction "2_2") (pintype "passive"))
    )
    (net (code "55") (name "GND") (class "Default")
      (node (ref "C100") (pin "2") (pinfunction "2_2") (pintype "passive"))
      (node (ref "C21") (pin "1") (pinfunction "1_1") (pintype "passive"))
      (node (ref "C22") (pin "1") (pinfunction "1_1") (pintype "passive"))
      (node (ref "C23") (pin "1") (pinfunction "1_1") (pintype "passive"))
      (node (ref "C24") (pin "1") (pinfunction "1_1") (pintype "passive"))
      (node (ref "C25") (pin "1") (pinfunction "1_1") (pintype "passive"))
      (node (ref "C26") (pin "1") (pinfunction "1_1") (pintype "passive"))
      (node (ref "C27") (pin "1") (pinfunction "1_1") (pintype "passive"))
      (node (ref "C28") (pin "1") (pinfunction "1_1") (pintype "passive"))
      (node (ref "C29") (pin "1") (pinfunction "1_1") (pintype "passive"))
      (node (ref "C30") (pin "1") (pinfunction "1_1") (pintype "passive"))
      (node (ref "C302") (pin "1") (pinfunction "1_1") (pintype "passive"))
      (node (ref "C303") (pin "1") (pinfunction "1_1") (pintype "passive"))
      (node (ref "C304") (pin "1") (pinfunction "1_1") (pintype "passive"))
      (node (ref "C305") (pin "1") (pinfunction "1_1") (pintype "passive"))
      (node (ref "C306") (pin "1") (pinfunction "1_1") (pintype "passive"))
      (node (ref "C307") (pin "1") (pinfunction "1_1") (pintype "passive"))
      (node (ref "C308") (pin "1") (pinfunction "1_1") (pintype "passive"))
      (node (ref "C309") (pin "1") (pinfunction "1_1") (pintype "passive"))
      (node (ref "C31") (pin "1") (pinfunction "1_1") (pintype "passive"))
      (node (ref "C310") (pin "1") (pinfunction "1_1") (pintype "passive"))
      (node (ref "C311") (pin "1") (pinfunction "1_1") (pintype "passive"))
      (node (ref "C312") (pin "1") (pinfunction "1_1") (pintype "passive"))
      (node (ref "C313") (pin "1") (pinfunction "1_1") (pintype "passive"))
      (node (ref "C314") (pin "1") (pinfunction "1_1") (pintype "passive"))
      (node (ref "C315") (pin "1") (pinfunction "1_1") (pintype "passive"))
      (node (ref "C32") (pin "1") (pinfunction "1_1") (pintype "passive"))
      (node (ref "C33") (pin "1") (pinfunction "1_1") (pintype "passive"))
      (node (ref "C34") (pin "1") (pinfunction "1_1") (pintype "passive"))
      (node (ref "C35") (pin "1") (pinfunction "1_1") (pintype "passive"))
      (node (ref "C36") (pin "1") (pinfunction "1_1") (pintype "passive"))
      (node (ref "C361") (pin "2") (pinfunction "2_2") (pintype "passive"))
      (node (ref "C362") (pin "2") (pinfunction "2_2") (pintype "passive"))
      (node (ref "C363") (pin "2") (pinfunction "2_2") (pintype "passive"))
      (node (ref "C364") (pin "2") (pinfunction "2_2") (pintype "passive"))
      (node (ref "C37") (pin "1") (pinfunction "1_1") (pintype "passive"))
      (node (ref "C379") (pin "2") (pinfunction "2_2") (pintype "passive"))
      (node (ref "C38") (pin "1") (pinfunction "1_1") (pintype "passive"))
      (node (ref "C380") (pin "2") (pinfunction "2_2") (pintype "passive"))
      (node (ref "C381") (pin "2") (pinfunction "2_2") (pintype "passive"))
      (node (ref "C382") (pin "2") (pinfunction "2_2") (pintype "passive"))
      (node (ref "C39") (pin "1") (pinfunction "1_1") (pintype "passive"))
      (node (ref "C40") (pin "1") (pinfunction "1_1") (pintype "passive"))
      (node (ref "C41") (pin "1") (pinfunction "1_1") (pintype "passive"))
      (node (ref "C42") (pin "1") (pinfunction "1_1") (pintype "passive"))
      (node (ref "C43") (pin "1") (pinfunction "1_1") (pintype "passive"))
      (node (ref "C44") (pin "1") (pinfunction "1_1") (pintype "passive"))
      (node (ref "C45") (pin "1") (pinfunction "1_1") (pintype "passive"))
      (node (ref "C456") (pin "2") (pinfunction "2_2") (pintype "passive"))
      (node (ref "C457") (pin "2") (pinfunction "2_2") (pintype "passive"))
      (node (ref "C458") (pin "2") (pinfunction "2_2") (pintype "passive"))
      (node (ref "C459") (pin "2") (pinfunction "2_2") (pintype "passive"))
      (node (ref "C46") (pin "1") (pinfunction "1_1") (pintype "passive"))
      (node (ref "C460") (pin "2") (pinfunction "2_2") (pintype "passive"))
      (node (ref "C461") (pin "2") (pinfunction "2_2") (pintype "passive"))
      (node (ref "C462") (pin "2") (pinfunction "2_2") (pintype "passive"))
      (node (ref "C47") (pin "1") (pinfunction "1_1") (pintype "passive"))
      (node (ref "C476") (pin "2") (pinfunction "2_2") (pintype "passive"))
      (node (ref "C476") (pin "4") (pinfunction "4_4") (pintype "passive"))
      (node (ref "C476") (pin "6") (pinfunction "6_6") (pintype "passive"))
      (node (ref "C476") (pin "8") (pinfunction "8_8") (pintype "passive"))
      (node (ref "C477") (pin "2") (pinfunction "2_2") (pintype "passive"))
      (node (ref "C477") (pin "4") (pinfunction "4_4") (pintype "passive"))
      (node (ref "C477") (pin "6") (pinfunction "6_6") (pintype "passive"))
      (node (ref "C477") (pin "8") (pinfunction "8_8") (pintype "passive"))
      (node (ref "C478") (pin "2") (pinfunction "2_2") (pintype "passive"))
      (node (ref "C478") (pin "4") (pinfunction "4_4") (pintype "passive"))
      (node (ref "C478") (pin "6") (pinfunction "6_6") (pintype "passive"))
      (node (ref "C478") (pin "8") (pinfunction "8_8") (pintype "passive"))
      (node (ref "C479") (pin "2") (pinfunction "2_2") (pintype "passive"))
      (node (ref "C479") (pin "4") (pinfunction "4_4") (pintype "passive"))
      (node (ref "C479") (pin "6") (pinfunction "6_6") (pintype "passive"))
      (node (ref "C479") (pin "8") (pinfunction "8_8") (pintype "passive"))
      (node (ref "C48") (pin "1") (pinfunction "1_1") (pintype "passive"))
      (node (ref "C480") (pin "2") (pinfunction "2_2") (pintype "passive"))
      (node (ref "C480") (pin "4") (pinfunction "4_4") (pintype "passive"))
      (node (ref "C480") (pin "6") (pinfunction "6_6") (pintype "passive"))
      (node (ref "C480") (pin "8") (pinfunction "8_8") (pintype "passive"))
      (node (ref "C481") (pin "2") (pinfunction "2_2") (pintype "passive"))
      (node (ref "C481") (pin "4") (pinfunction "4_4") (pintype "passive"))
      (node (ref "C481") (pin "6") (pinfunction "6_6") (pintype "passive"))
      (node (ref "C481") (pin "8") (pinfunction "8_8") (pintype "passive"))
      (node (ref "C488") (pin "2") (pinfunction "2_2") (pintype "passive"))
      (node (ref "C489") (pin "2") (pinfunction "2_2") (pintype "passive"))
      (node (ref "C49") (pin "1") (pinfunction "1_1") (pintype "passive"))
      (node (ref "C490") (pin "2") (pinfunction "2_2") (pintype "passive"))
      (node (ref "C491") (pin "2") (pinfunction "2_2") (pintype "passive"))
      (node (ref "C492") (pin "2") (pinfunction "2_2") (pintype "passive"))
      (node (ref "C493") (pin "2") (pinfunction "2_2") (pintype "passive"))
      (node (ref "C50") (pin "1") (pinfunction "1_1") (pintype "passive"))
      (node (ref "C51") (pin "1") (pinfunction "1_1") (pintype "passive"))
      (node (ref "C52") (pin "1") (pinfunction "1_1") (pintype "passive"))
      (node (ref "C53") (pin "1") (pinfunction "1_1") (pintype "passive"))
      (node (ref "C54") (pin "1") (pinfunction "1_1") (pintype "passive"))
      (node (ref "C55") (pin "1") (pinfunction "1_1") (pintype "passive"))
      (node (ref "C56") (pin "1") (pinfunction "1_1") (pintype "passive"))
      (node (ref "C57") (pin "1") (pinfunction "1_1") (pintype "passive"))
      (node (ref "C58") (pin "1") (pinfunction "1_1") (pintype "passive"))
      (node (ref "C59") (pin "1") (pinfunction "1_1") (pintype "passive"))
      (node (ref "C60") (pin "1") (pinfunction "1_1") (pintype "passive"))
      (node (ref "C61") (pin "1") (pinfunction "1_1") (pintype "passive"))
      (node (ref "C62") (pin "1") (pinfunction "1_1") (pintype "passive"))
      (node (ref "C63") (pin "1") (pinfunction "1_1") (pintype "passive"))
      (node (ref "C64") (pin "1") (pinfunction "1_1") (pintype "passive"))
      (node (ref "C65") (pin "1") (pinfunction "1_1") (pintype "passive"))
      (node (ref "C66") (pin "1") (pinfunction "1_1") (pintype "passive"))
      (node (ref "C67") (pin "1") (pinfunction "1_1") (pintype "passive"))
      (node (ref "C68") (pin "1") (pinfunction "1_1") (pintype "passive"))
      (node (ref "C69") (pin "1") (pinfunction "1_1") (pintype "passive"))
      (node (ref "C70") (pin "1") (pinfunction "1_1") (pintype "passive"))
      (node (ref "C71") (pin "1") (pinfunction "1_1") (pintype "passive"))
      (node (ref "C72") (pin "1") (pinfunction "1_1") (pintype "passive"))
      (node (ref "C73") (pin "1") (pinfunction "1_1") (pintype "passive"))
      (node (ref "C74") (pin "1") (pinfunction "1_1") (pintype "passive"))
      (node (ref "C75") (pin "1") (pinfunction "1_1") (pintype "passive"))
      (node (ref "C76") (pin "1") (pinfunction "1_1") (pintype "passive"))
      (node (ref "C77") (pin "1") (pinfunction "1_1") (pintype "passive"))
      (node (ref "C78") (pin "1") (pinfunction "1_1") (pintype "passive"))
      (node (ref "C79") (pin "1") (pinfunction "1_1") (pintype "passive"))
      (node (ref "C80") (pin "1") (pinfunction "1_1") (pintype "passive"))
      (node (ref "C81") (pin "1") (pinfunction "1_1") (pintype "passive"))
      (node (ref "C82") (pin "1") (pinfunction "1_1") (pintype "passive"))
      (node (ref "C83") (pin "1") (pinfunction "1_1") (pintype "passive"))
      (node (ref "C84") (pin "1") (pinfunction "1_1") (pintype "passive"))
      (node (ref "C96") (pin "2") (pinfunction "2_2") (pintype "passive"))
      (node (ref "C97") (pin "2") (pinfunction "2_2") (pintype "passive"))
      (node (ref "C98") (pin "2") (pinfunction "2_2") (pintype "passive"))
      (node (ref "C99") (pin "2") (pinfunction "2_2") (pintype "passive"))
      (node (ref "IC10") (pin "11") (pinfunction "GND_11") (pintype "power_in"))
      (node (ref "IC10") (pin "5") (pinfunction "ILIM_5") (pintype "input"))
      (node (ref "IC10") (pin "8") (pinfunction "GND_8") (pintype "power_in"))
      (node (ref "IC11") (pin "11") (pinfunction "GND_11") (pintype "power_in"))
      (node (ref "IC11") (pin "5") (pinfunction "ILIM_5") (pintype "input"))
      (node (ref "IC11") (pin "8") (pinfunction "GND_8") (pintype "power_in"))
      (node (ref "IC12") (pin "11") (pinfunction "GND_11") (pintype "power_in"))
      (node (ref "IC12") (pin "5") (pinfunction "ILIM_5") (pintype "input"))
      (node (ref "IC12") (pin "8") (pinfunction "GND_8") (pintype "power_in"))
      (node (ref "IC13") (pin "11") (pinfunction "GND_11") (pintype "power_in"))
      (node (ref "IC13") (pin "5") (pinfunction "ILIM_5") (pintype "input"))
      (node (ref "IC13") (pin "8") (pinfunction "GND_8") (pintype "power_in"))
      (node (ref "IC5") (pin "89") (pinfunction "EP_89") (pintype "power_in"))
      (node (ref "IC7") (pin "11") (pinfunction "GND_11") (pintype "power_in"))
      (node (ref "IC7") (pin "5") (pinfunction "ILIM_5") (pintype "input"))
      (node (ref "IC7") (pin "8") (pinfunction "GND_8") (pintype "power_in"))
      (node (ref "IC8") (pin "11") (pinfunction "GND_11") (pintype "power_in"))
      (node (ref "IC8") (pin "5") (pinfunction "ILIM_5") (pintype "input"))
      (node (ref "IC8") (pin "8") (pinfunction "GND_8") (pintype "power_in"))
      (node (ref "IC9") (pin "11") (pinfunction "GND_11") (pintype "power_in"))
      (node (ref "IC9") (pin "5") (pinfunction "ILIM_5") (pintype "input"))
      (node (ref "IC9") (pin "8") (pinfunction "GND_8") (pintype "power_in"))
      (node (ref "R187") (pin "2") (pinfunction "2_2") (pintype "passive"))
      (node (ref "R188") (pin "1") (pinfunction "1_1") (pintype "passive"))
      (node (ref "R189") (pin "1") (pinfunction "1_1") (pintype "passive"))
      (node (ref "R190") (pin "1") (pinfunction "1_1") (pintype "passive"))
      (node (ref "R191") (pin "1") (pinfunction "1_1") (pintype "passive"))
      (node (ref "R192") (pin "1") (pinfunction "1_1") (pintype "passive"))
      (node (ref "R193") (pin "1") (pinfunction "1_1") (pintype "passive"))
      (node (ref "R194") (pin "1") (pinfunction "1_1") (pintype "passive"))
    )
    (net (code "56") (name "Net-(C380-Pad1)") (class "Default")
      (node (ref "C380") (pin "1") (pinfunction "1_1") (pintype "passive"))
      (node (ref "R28") (pin "2") (pinfunction "2_2") (pintype "passive"))
    )
    (net (code "57") (name "Net-(C381-Pad1)") (class "Default")
      (node (ref "C381") (pin "1") (pinfunction "1_1") (pintype "passive"))
      (node (ref "R29") (pin "2") (pinfunction "2_2") (pintype "passive"))
    )
    (net (code "58") (name "Net-(IC5-I120)") (class "Default")
      (node (ref "IC5") (pin "86") (pinfunction "I120_86") (pintype "output"))
      (node (ref "R187") (pin "1") (pinfunction "1_1") (pintype "passive"))
    )
    (net (code "59") (name "Net-(IC5-LDO_BYP1)") (class "Default")
      (node (ref "IC5") (pin "34") (pinfunction "LDO_BYP1_34") (pintype "input"))
      (node (ref "R29") (pin "1") (pinfunction "1_1") (pintype "passive"))
    )
    (net (code "60") (name "Net-(IC5-LDO_BYP2)") (class "Default")
      (node (ref "IC5") (pin "88") (pinfunction "LDO_BYP2_88") (pintype "input"))
      (node (ref "R28") (pin "1") (pinfunction "1_1") (pintype "passive"))
    )
    (net (code "61") (name "Net-(IC7-SET)") (class "Default")
      (node (ref "C457") (pin "1") (pinfunction "1_1") (pintype "passive"))
      (node (ref "IC7") (pin "7") (pinfunction "SET_7") (pintype "input"))
      (node (ref "R192") (pin "2") (pinfunction "2_2") (pintype "passive"))
    )
    (net (code "62") (name "Net-(IC8-SET)") (class "Default")
      (node (ref "C456") (pin "1") (pinfunction "1_1") (pintype "passive"))
      (node (ref "IC8") (pin "7") (pinfunction "SET_7") (pintype "input"))
      (node (ref "R189") (pin "2") (pinfunction "2_2") (pintype "passive"))
    )
    (net (code "63") (name "Net-(IC9-SET)") (class "Default")
      (node (ref "C458") (pin "1") (pinfunction "1_1") (pintype "passive"))
      (node (ref "IC9") (pin "7") (pinfunction "SET_7") (pintype "input"))
      (node (ref "R190") (pin "2") (pinfunction "2_2") (pintype "passive"))
    )
    (net (code "64") (name "Net-(IC10-SET)") (class "Default")
      (node (ref "C459") (pin "1") (pinfunction "1_1") (pintype "passive"))
      (node (ref "IC10") (pin "7") (pinfunction "SET_7") (pintype "input"))
      (node (ref "R193") (pin "2") (pinfunction "2_2") (pintype "passive"))
    )
    (net (code "65") (name "Net-(IC11-SET)") (class "Default")
      (node (ref "C460") (pin "1") (pinfunction "1_1") (pintype "passive"))
      (node (ref "IC11") (pin "7") (pinfunction "SET_7") (pintype "input"))
      (node (ref "R194") (pin "2") (pinfunction "2_2") (pintype "passive"))
    )
    (net (code "66") (name "Net-(IC12-SET)") (class "Default")
      (node (ref "C461") (pin "1") (pinfunction "1_1") (pintype "passive"))
      (node (ref "IC12") (pin "7") (pinfunction "SET_7") (pintype "input"))
      (node (ref "R191") (pin "2") (pinfunction "2_2") (pintype "passive"))
    )
    (net (code "67") (name "Net-(IC13-SET)") (class "Default")
      (node (ref "C462") (pin "1") (pinfunction "1_1") (pintype "passive"))
      (node (ref "IC13") (pin "7") (pinfunction "SET_7") (pintype "input"))
      (node (ref "R188") (pin "2") (pinfunction "2_2") (pintype "passive"))
    )
    (net (code "68") (name "P2V0") (class "Default")
      (node (ref "C303") (pin "2") (pinfunction "2_2") (pintype "passive"))
      (node (ref "C305") (pin "2") (pinfunction "2_2") (pintype "passive"))
      (node (ref "C307") (pin "2") (pinfunction "2_2") (pintype "passive"))
      (node (ref "C309") (pin "2") (pinfunction "2_2") (pintype "passive"))
      (node (ref "C311") (pin "2") (pinfunction "2_2") (pintype "passive"))
      (node (ref "C313") (pin "2") (pinfunction "2_2") (pintype "passive"))
      (node (ref "IC10") (pin "1") (pinfunction "IN_1") (pintype "input"))
      (node (ref "IC10") (pin "2") (pinfunction "IN_2") (pintype "input"))
      (node (ref "IC10") (pin "3") (pinfunction "EN/UV_3") (pintype "input"))
      (node (ref "IC10") (pin "6") (pinfunction "PGFB_6") (pintype "input"))
      (node (ref "IC11") (pin "1") (pinfunction "IN_1") (pintype "input"))
      (node (ref "IC11") (pin "2") (pinfunction "IN_2") (pintype "input"))
      (node (ref "IC11") (pin "3") (pinfunction "EN/UV_3") (pintype "input"))
      (node (ref "IC11") (pin "6") (pinfunction "PGFB_6") (pintype "input"))
      (node (ref "IC12") (pin "1") (pinfunction "IN_1") (pintype "input"))
      (node (ref "IC12") (pin "2") (pinfunction "IN_2") (pintype "input"))
      (node (ref "IC12") (pin "3") (pinfunction "EN/UV_3") (pintype "input"))
      (node (ref "IC12") (pin "6") (pinfunction "PGFB_6") (pintype "input"))
      (node (ref "IC7") (pin "1") (pinfunction "IN_1") (pintype "input"))
      (node (ref "IC7") (pin "2") (pinfunction "IN_2") (pintype "input"))
      (node (ref "IC7") (pin "3") (pinfunction "EN/UV_3") (pintype "input"))
      (node (ref "IC7") (pin "6") (pinfunction "PGFB_6") (pintype "input"))
      (node (ref "IC8") (pin "1") (pinfunction "IN_1") (pintype "input"))
      (node (ref "IC8") (pin "2") (pinfunction "IN_2") (pintype "input"))
      (node (ref "IC8") (pin "3") (pinfunction "EN/UV_3") (pintype "input"))
      (node (ref "IC8") (pin "6") (pinfunction "PGFB_6") (pintype "input"))
      (node (ref "IC9") (pin "1") (pinfunction "IN_1") (pintype "input"))
      (node (ref "IC9") (pin "2") (pinfunction "IN_2") (pintype "input"))
      (node (ref "IC9") (pin "3") (pinfunction "EN/UV_3") (pintype "input"))
      (node (ref "IC9") (pin "6") (pinfunction "PGFB_6") (pintype "input"))
    )
    (net (code "69") (name "P2V5F") (class "Default")
      (node (ref "L14") (pin "1") (pinfunction "1_1") (pintype "passive"))
    )
    (net (code "70") (name "P4V0") (class "Default")
      (node (ref "C315") (pin "2") (pinfunction "2_2") (pintype "passive"))
      (node (ref "IC13") (pin "1") (pinfunction "IN_1") (pintype "input"))
      (node (ref "IC13") (pin "2") (pinfunction "IN_2") (pintype "input"))
      (node (ref "IC13") (pin "3") (pinfunction "EN/UV_3") (pintype "input"))
      (node (ref "IC13") (pin "6") (pinfunction "PGFB_6") (pintype "input"))
    )
    (net (code "71") (name "unconnected-(IC5-DNC-Pad54)") (class "Default")
      (node (ref "IC5") (pin "54") (pinfunction "DNC_54") (pintype "passive+no_connect"))
    )
    (net (code "72") (name "unconnected-(IC5-DNC-Pad55)") (class "Default")
      (node (ref "IC5") (pin "55") (pinfunction "DNC_55") (pintype "passive+no_connect"))
    )
    (net (code "73") (name "unconnected-(IC5-PDP_OUT0-Pad59)") (class "Default")
      (node (ref "IC5") (pin "59") (pinfunction "PDP_OUT0_59") (pintype "output+no_connect"))
    )
    (net (code "74") (name "unconnected-(IC5-PDP_OUT1-Pad58)") (class "Default")
      (node (ref "IC5") (pin "58") (pinfunction "PDP_OUT1_58") (pintype "output+no_connect"))
    )
    (net (code "75") (name "unconnected-(IC5-~{SYNCOUT1+}-Pad44)") (class "Default")
      (node (ref "IC5") (pin "44") (pinfunction "~{SYNCOUT1+}_44") (pintype "output+no_connect"))
    )
    (net (code "76") (name "unconnected-(IC5-~{SYNCOUT1-}-Pad43)") (class "Default")
      (node (ref "IC5") (pin "43") (pinfunction "~{SYNCOUT1-}_43") (pintype "output+no_connect"))
    )
    (net (code "77") (name "unconnected-(IC7-PG-Pad4)") (class "Default")
      (node (ref "IC7") (pin "4") (pinfunction "PG_4") (pintype "output+no_connect"))
    )
    (net (code "78") (name "unconnected-(IC8-PG-Pad4)") (class "Default")
      (node (ref "IC8") (pin "4") (pinfunction "PG_4") (pintype "output+no_connect"))
    )
    (net (code "79") (name "unconnected-(IC9-PG-Pad4)") (class "Default")
      (node (ref "IC9") (pin "4") (pinfunction "PG_4") (pintype "output+no_connect"))
    )
    (net (code "80") (name "unconnected-(IC10-PG-Pad4)") (class "Default")
      (node (ref "IC10") (pin "4") (pinfunction "PG_4") (pintype "output+no_connect"))
    )
    (net (code "81") (name "unconnected-(IC11-PG-Pad4)") (class "Default")
      (node (ref "IC11") (pin "4") (pinfunction "PG_4") (pintype "output+no_connect"))
    )
    (net (code "82") (name "unconnected-(IC12-PG-Pad4)") (class "Default")
      (node (ref "IC12") (pin "4") (pinfunction "PG_4") (pintype "output+no_connect"))
    )
    (net (code "83") (name "unconnected-(IC13-PG-Pad4)") (class "Default")
      (node (ref "IC13") (pin "4") (pinfunction "PG_4") (pintype "output+no_connect"))
    )
  )
)
